# BMS_Master.net
KiCad netlist of a schematic drawn in EAGLE
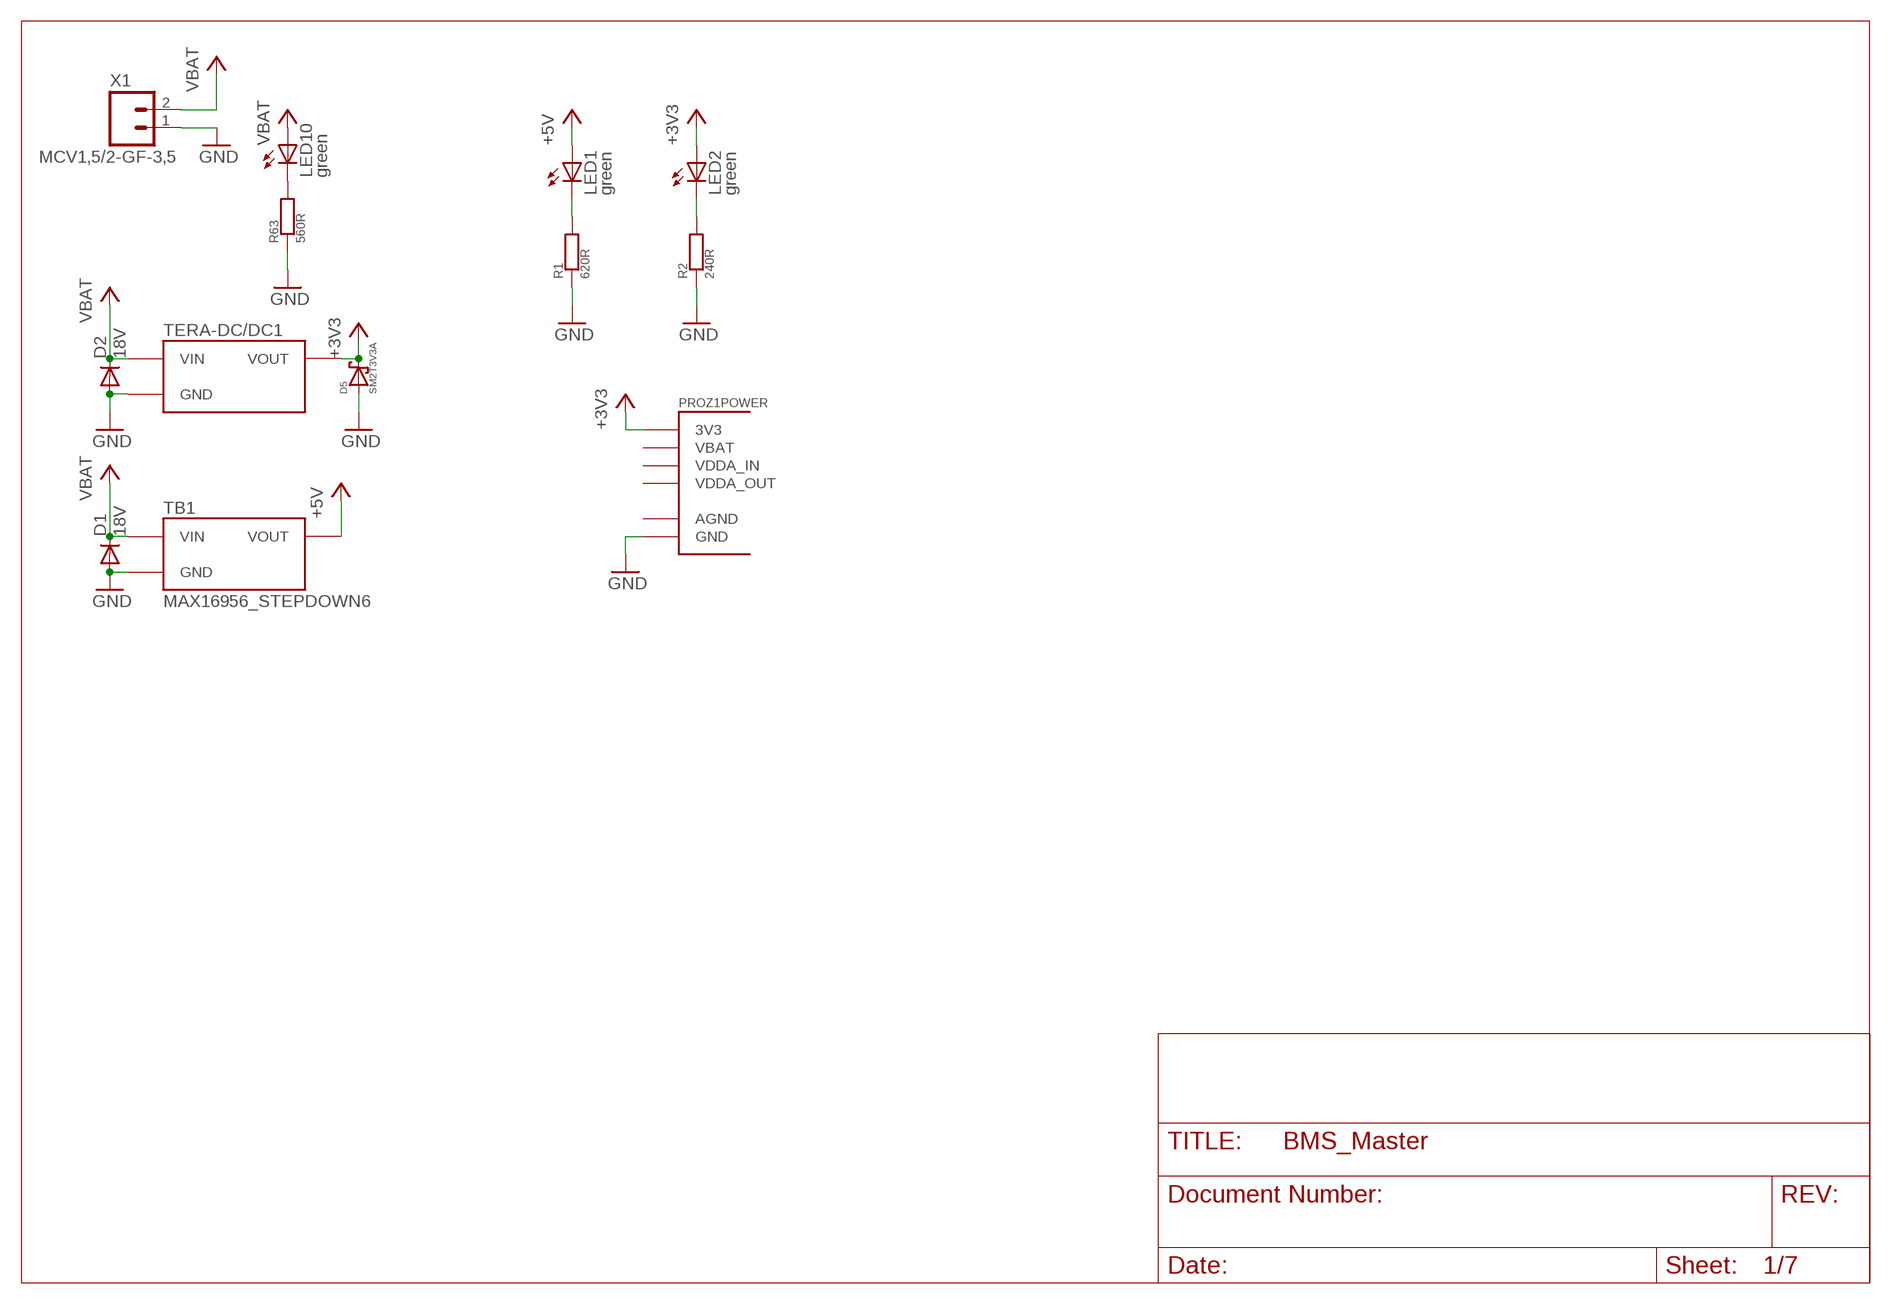
[diagram p0: schematic, sheet 1]
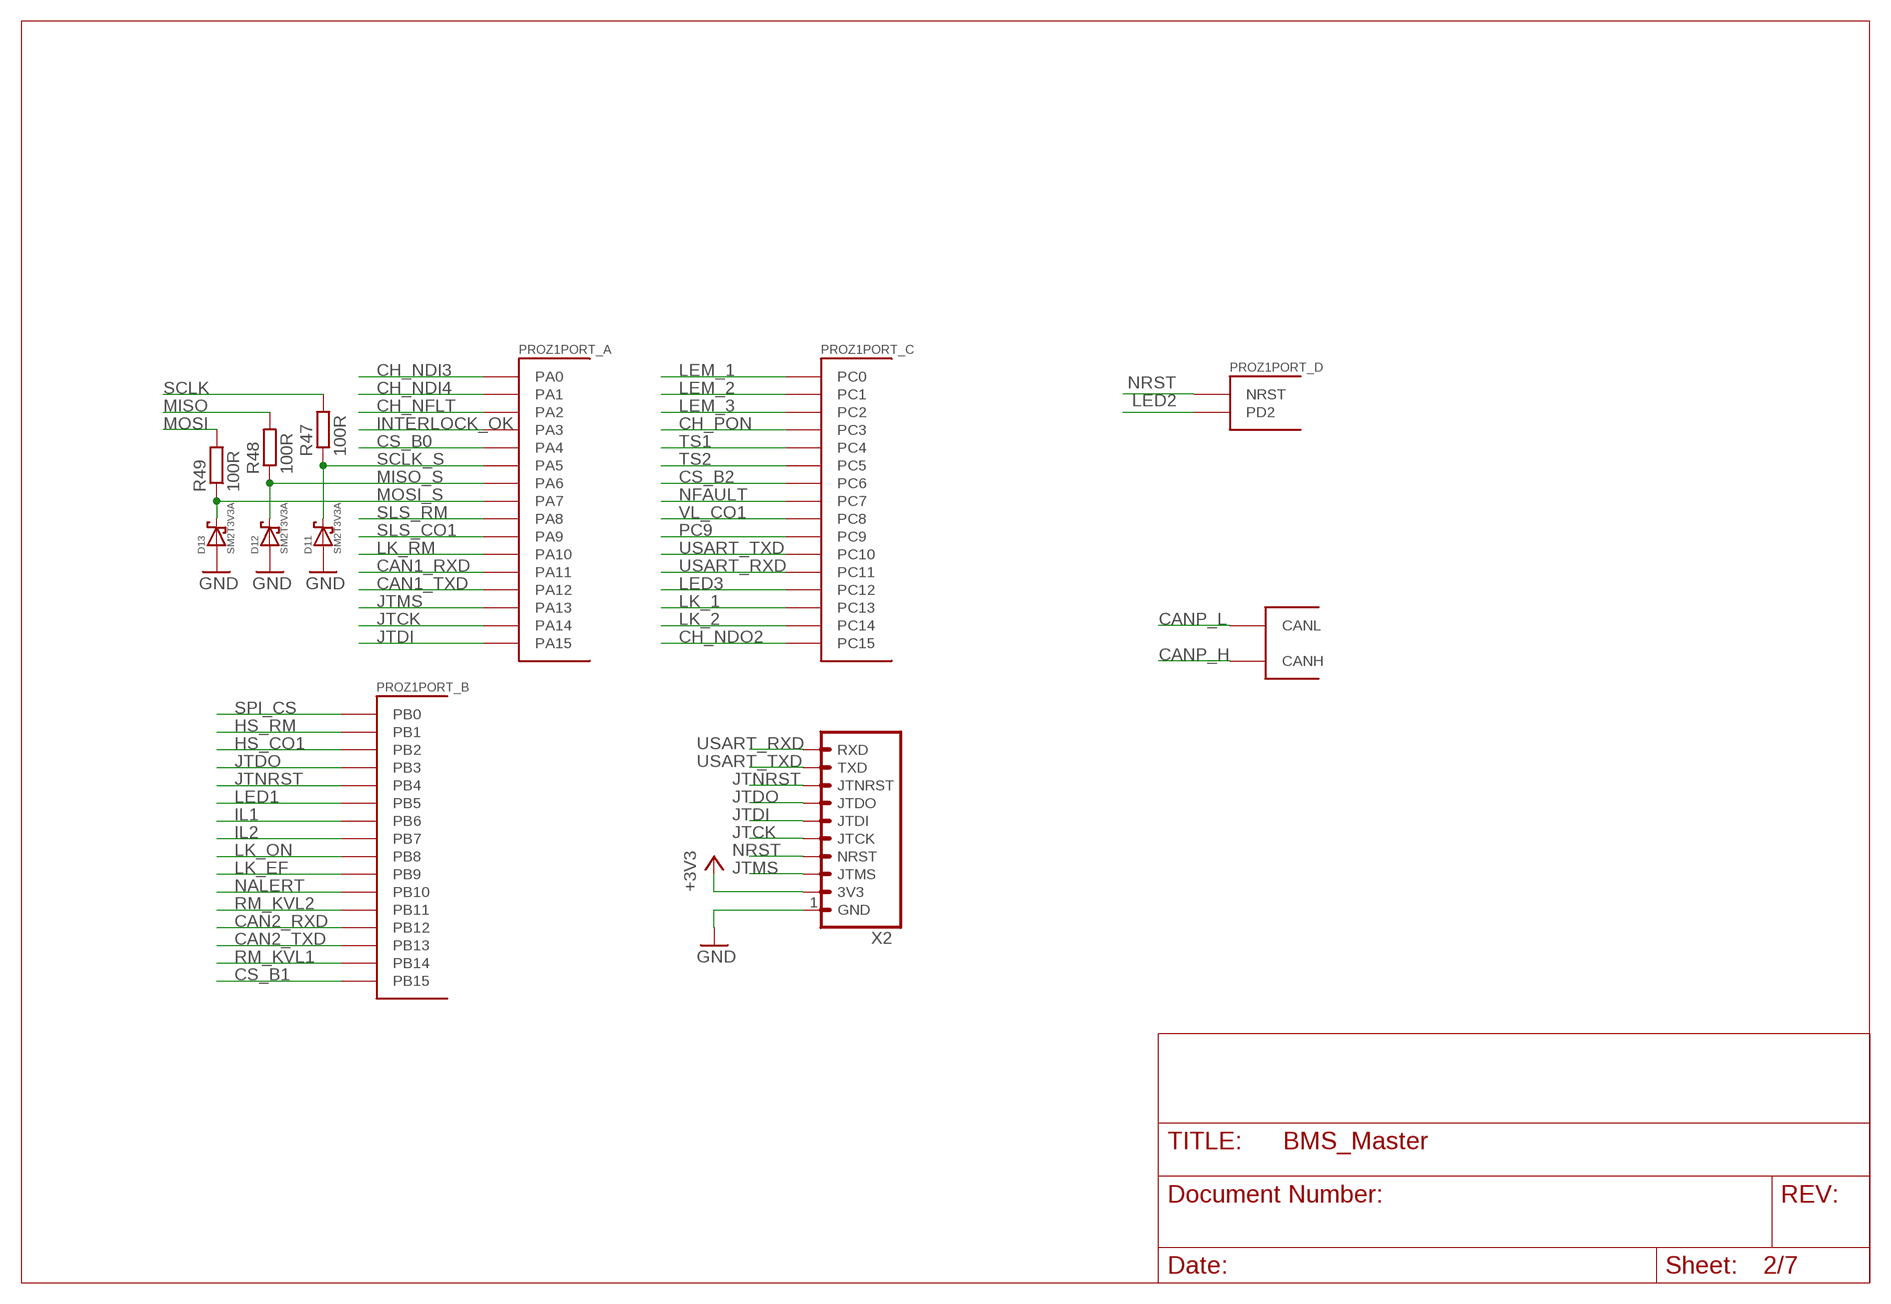
[diagram p1: schematic, sheet 2]
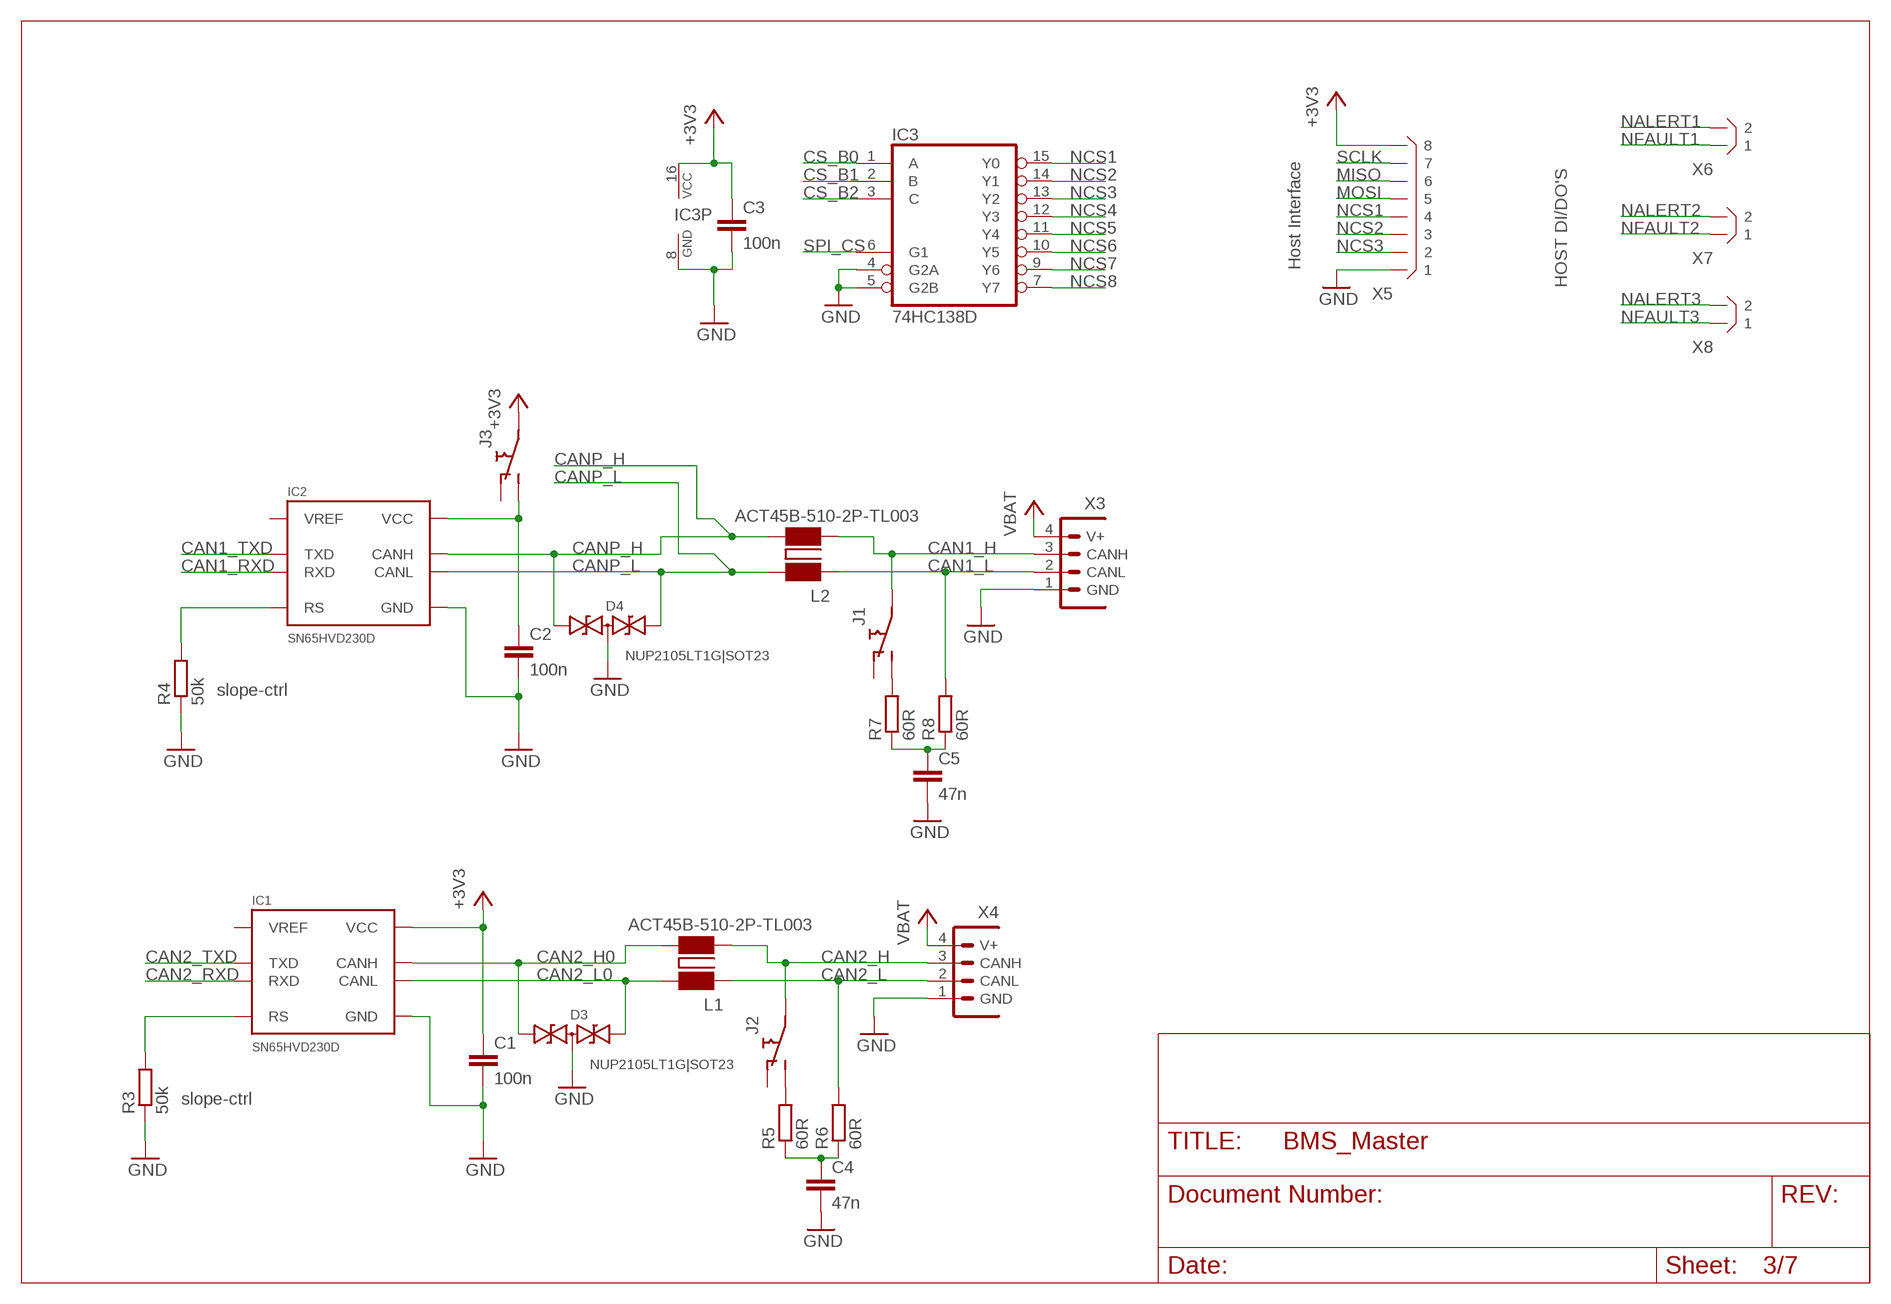
[diagram p2: schematic, sheet 3]
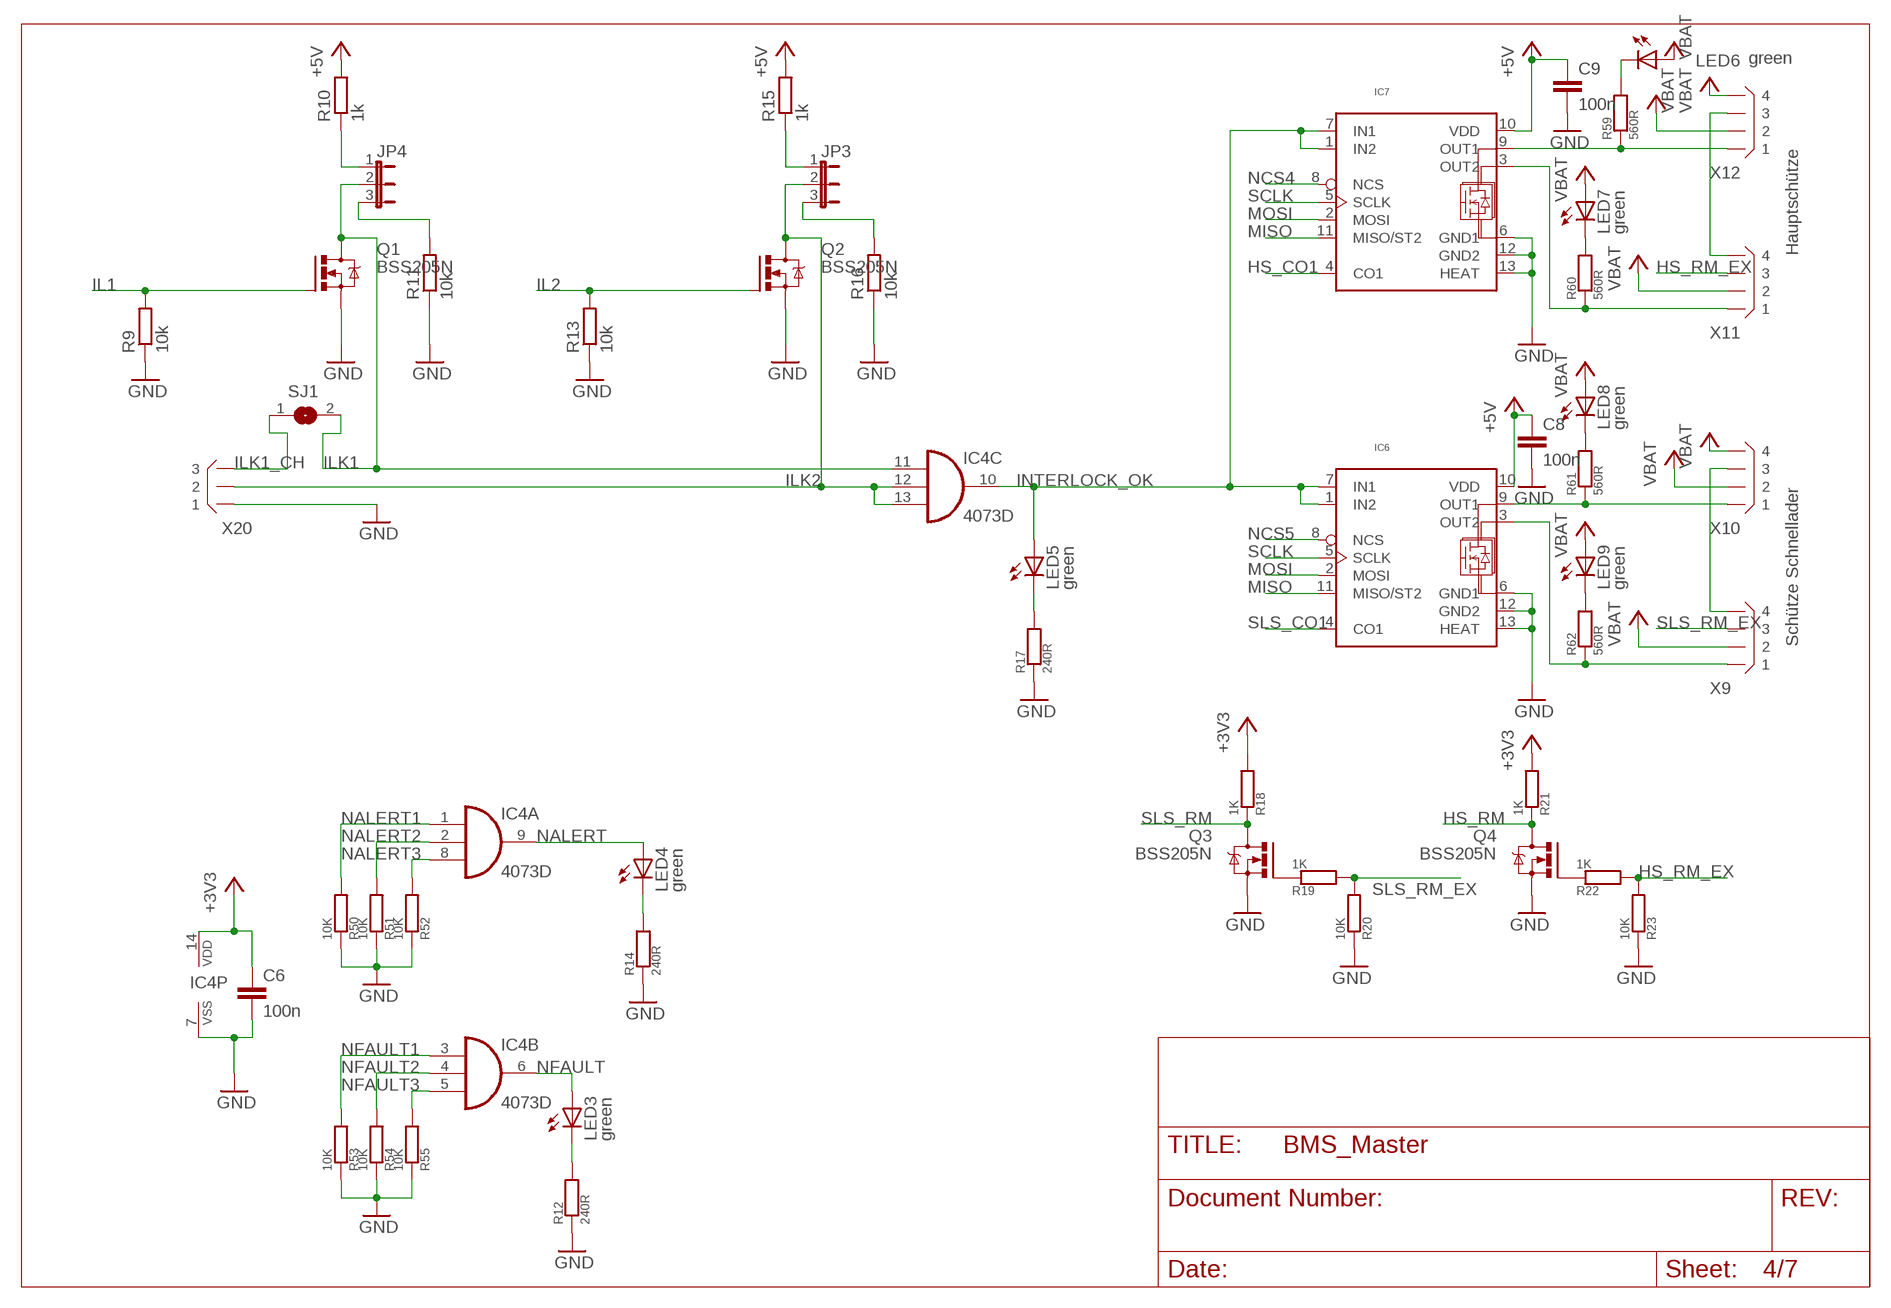
[diagram p3: schematic, sheet 4]
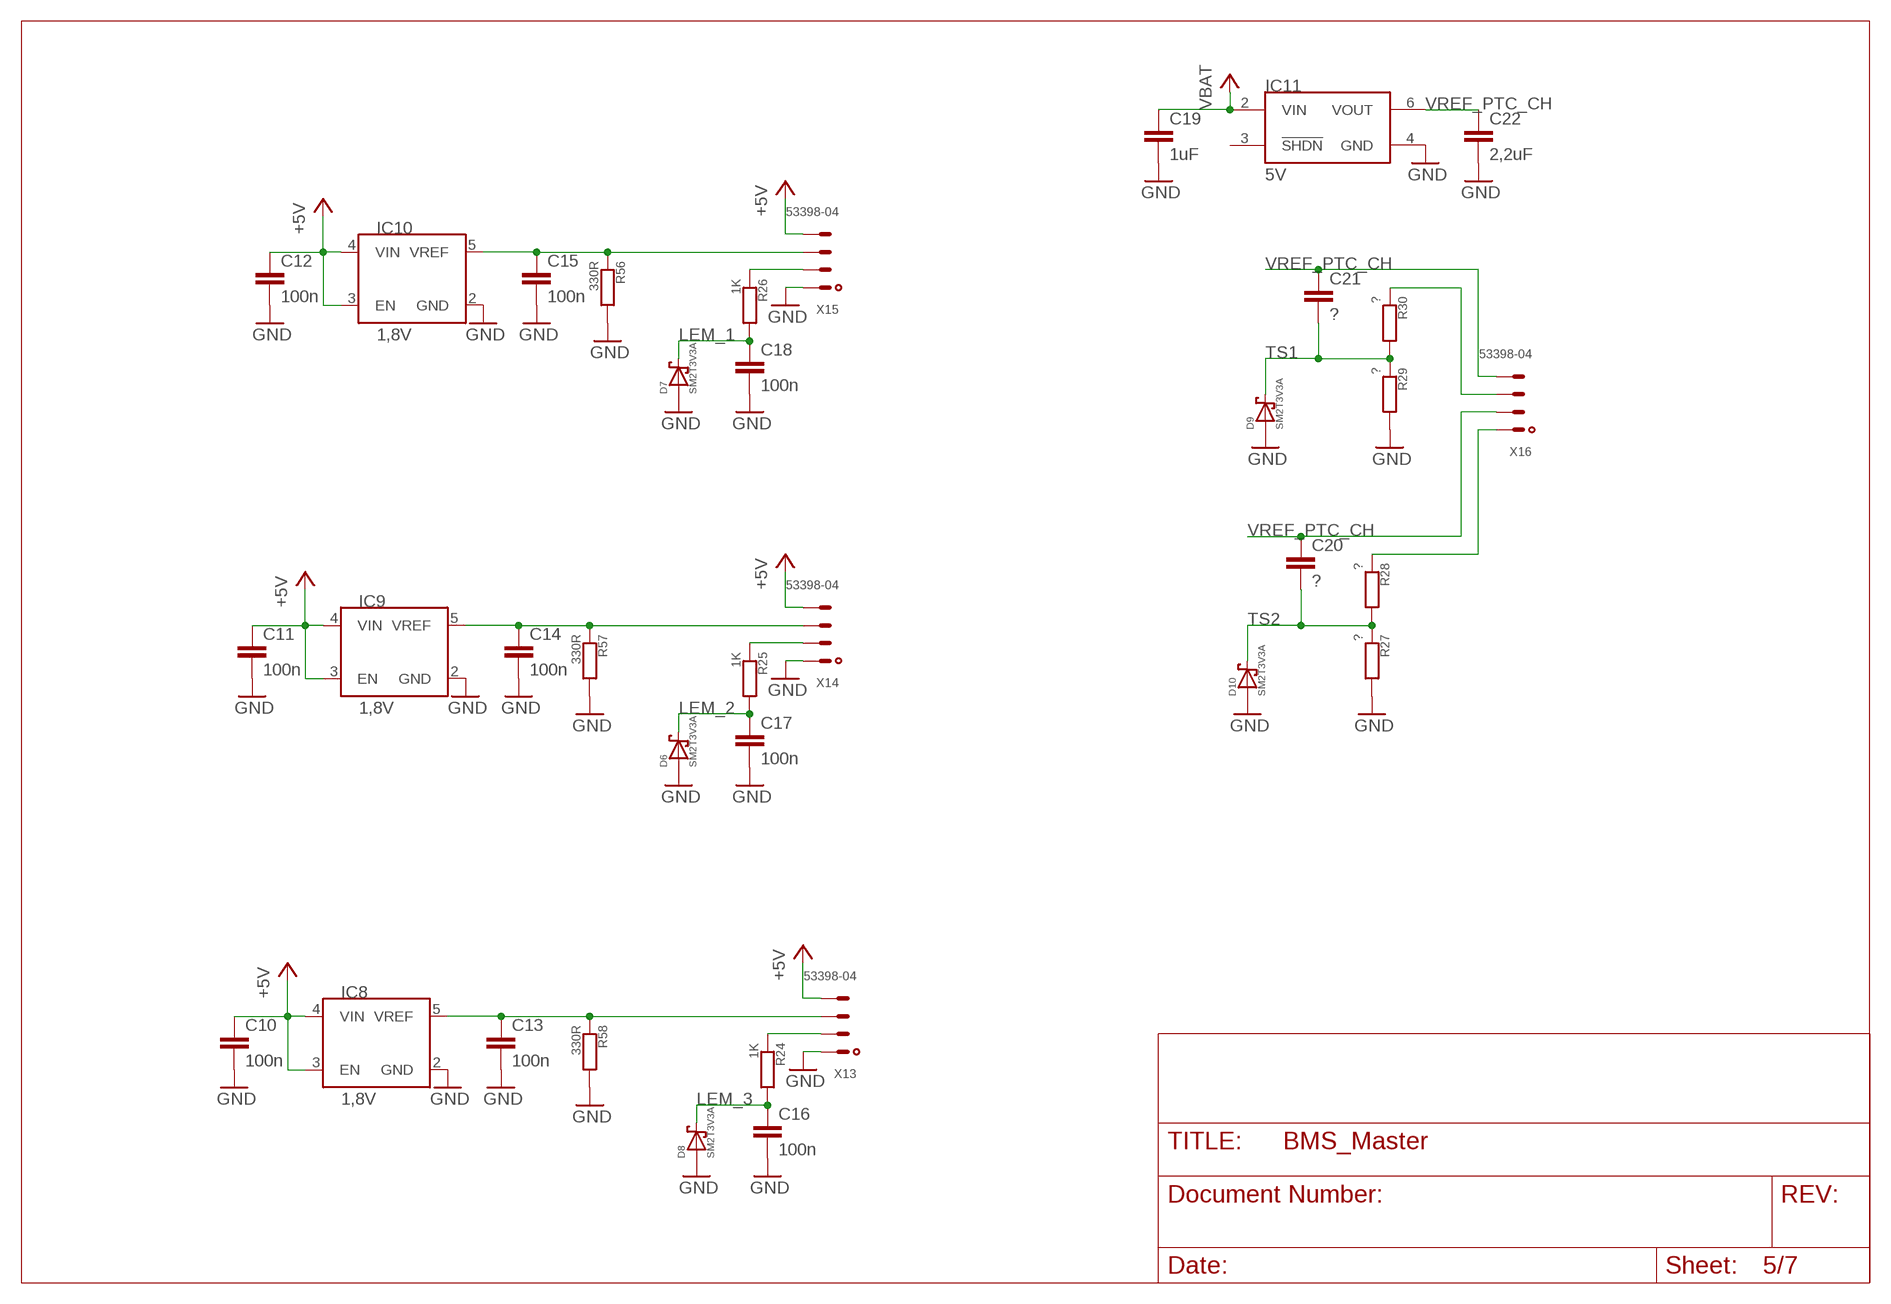
[diagram p4: schematic, sheet 5]
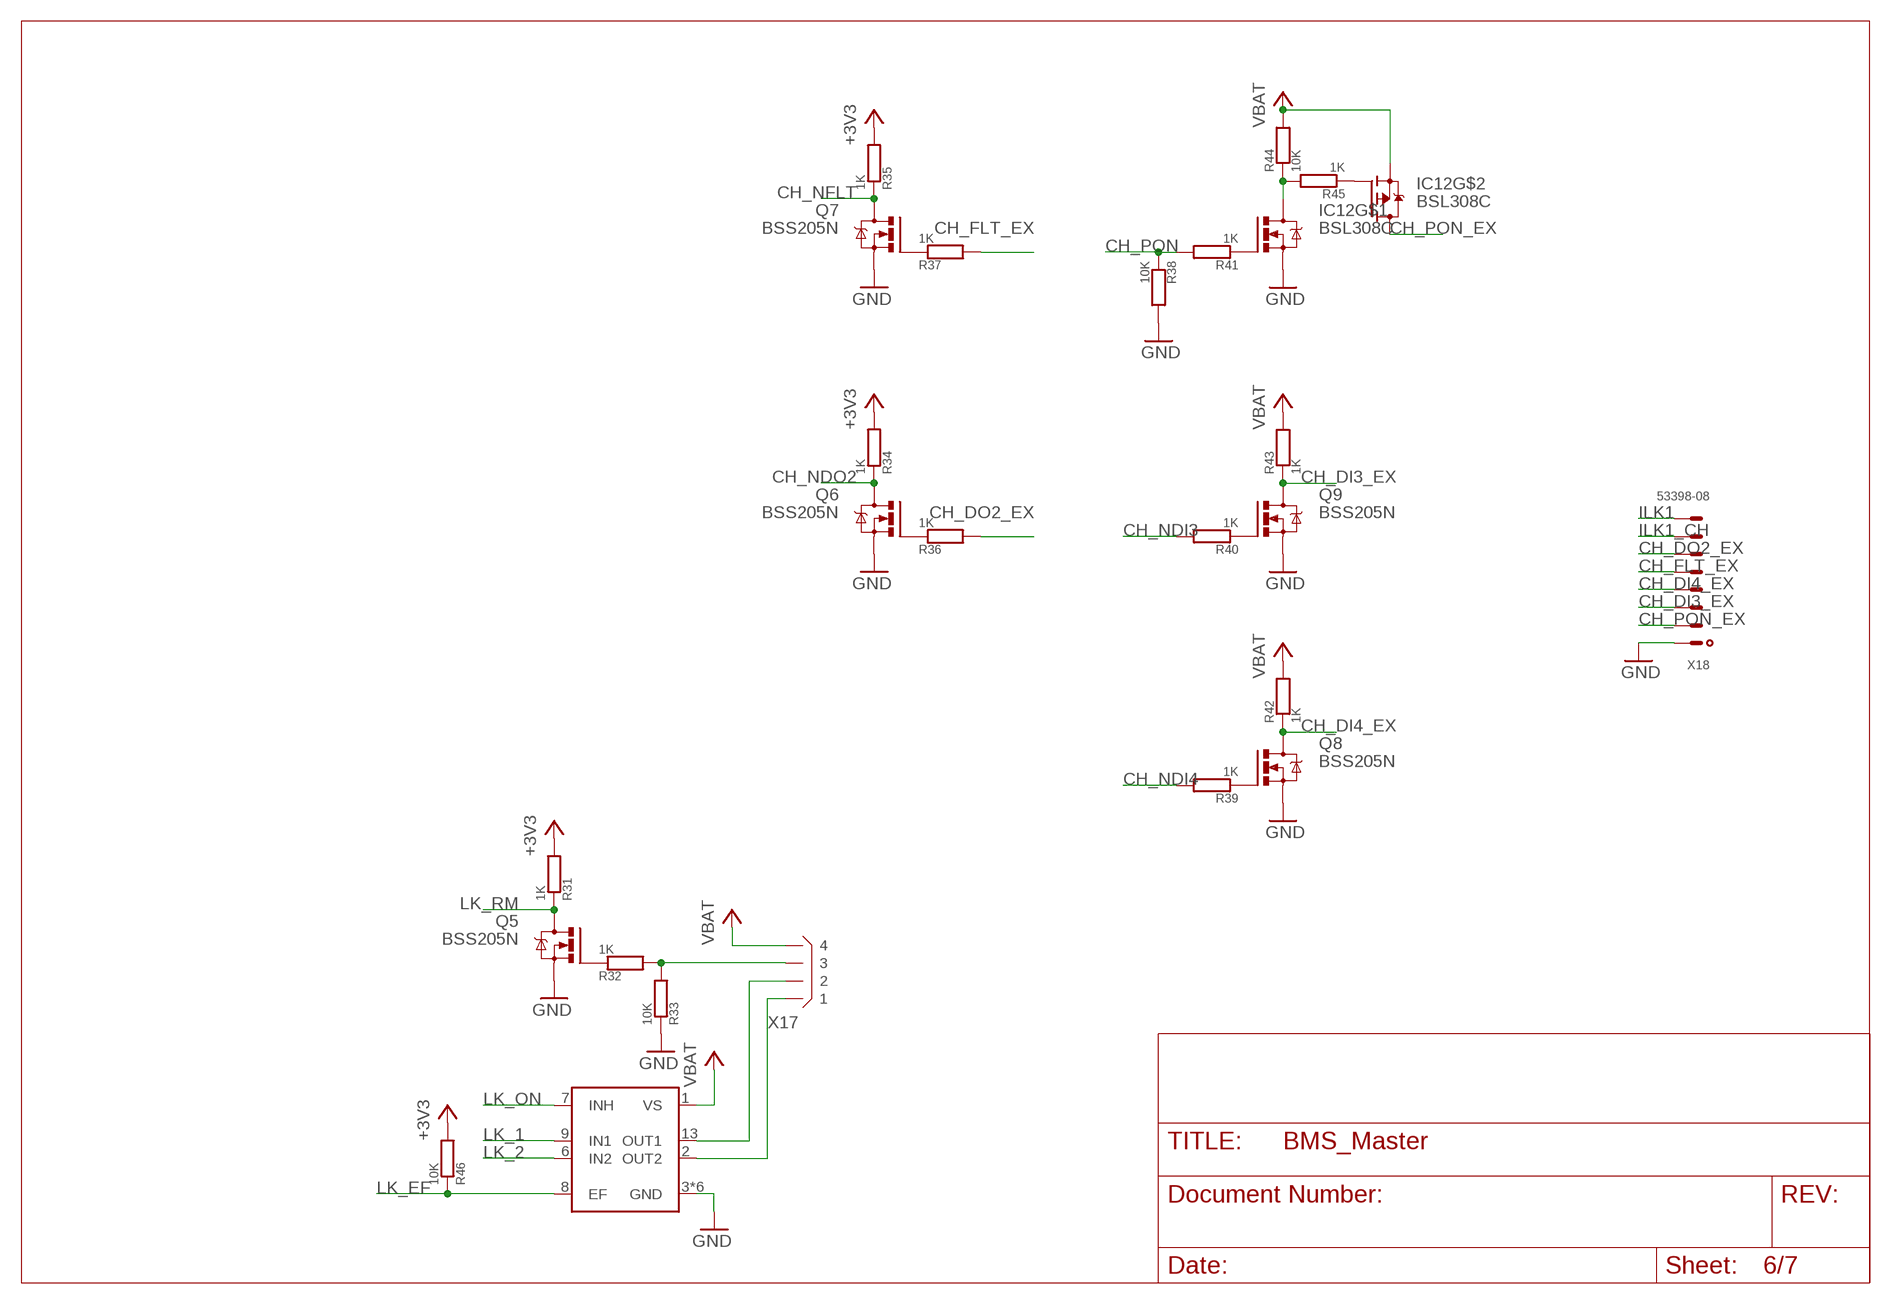
[diagram p5: schematic, sheet 6]
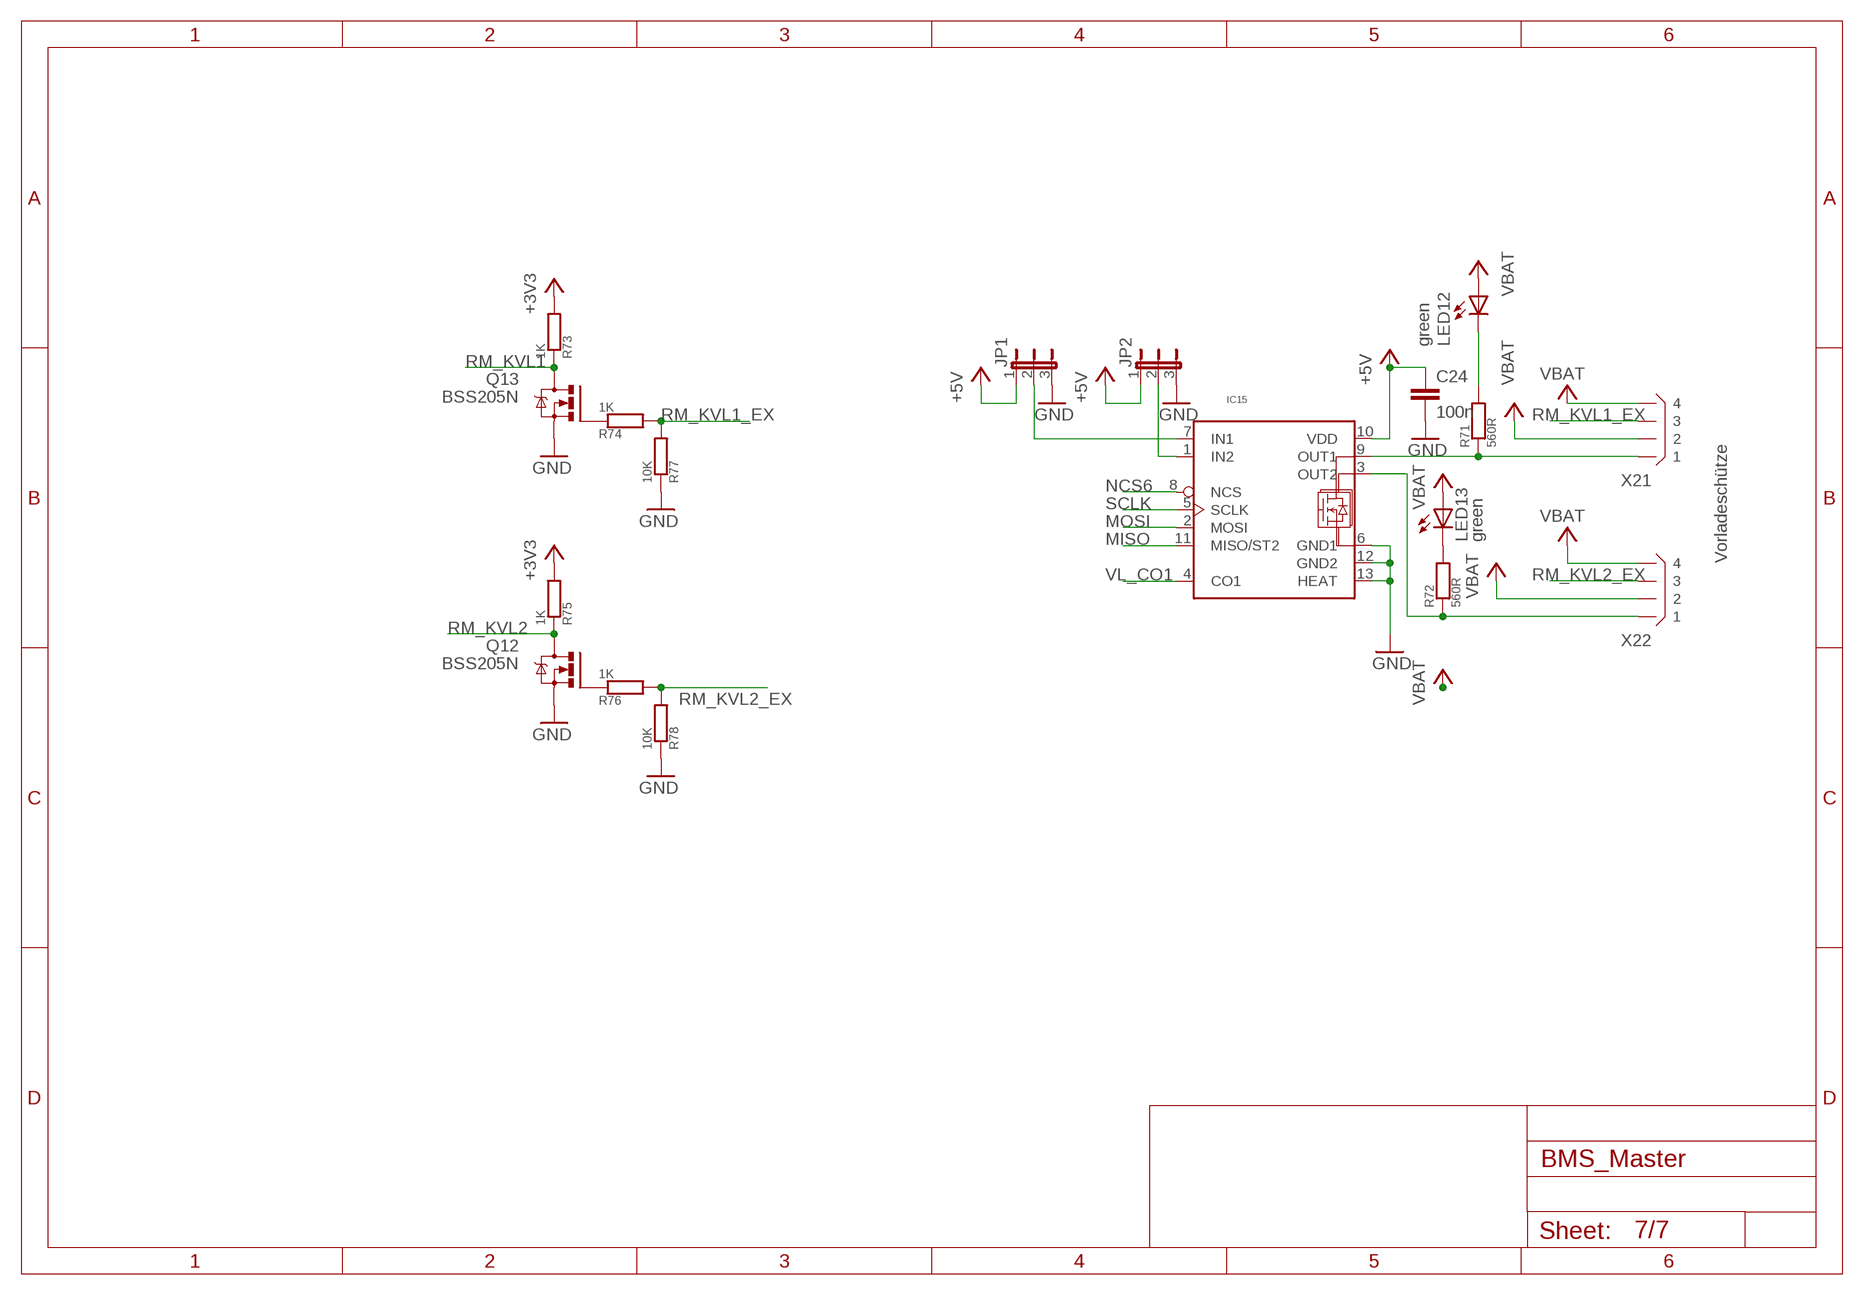
[diagram p6: schematic, sheet 7]

(export (version "E")
  (design (tool "Eeschema 10.0.6"))
  (components
    (comp (ref "D11")
      (value "SM2T3V3A")
      (footprint "eagle-import:SM2T3V3A")
      (libsource (lib "eagle-import") (part "SM2T3V3A"))
    )
    (comp (ref "D12")
      (value "SM2T3V3A")
      (footprint "eagle-import:SM2T3V3A")
      (libsource (lib "eagle-import") (part "SM2T3V3A"))
    )
    (comp (ref "D13")
      (value "SM2T3V3A")
      (footprint "eagle-import:SM2T3V3A")
      (libsource (lib "eagle-import") (part "SM2T3V3A"))
    )
    (comp (ref "PROZ1")
      (value "STM32F4_PROZESSORBOARDRPZ")
      (footprint "eagle-import:STM32F4_PROZESSORBOARD")
      (libsource (lib "eagle-import") (part "STM32F4_PROZESSORBOARDRPZ"))
    )
    (comp (ref "R47")
      (value "100R")
      (footprint "eagle-import:R0805")
      (libsource (lib "eagle-import") (part "R-EU_R0805"))
    )
    (comp (ref "R48")
      (value "100R")
      (footprint "eagle-import:R0805")
      (libsource (lib "eagle-import") (part "R-EU_R0805"))
    )
    (comp (ref "R49")
      (value "100R")
      (footprint "eagle-import:R0805")
      (libsource (lib "eagle-import") (part "R-EU_R0805"))
    )
    (comp (ref "X2")
      (value "TERA-PROG-DEBUG-10GERADE")
      (footprint "eagle-import:90130-1110")
      (libsource (lib "eagle-import") (part "TERA-PROG-DEBUG-10GERADE"))
    )
    (comp (ref "C24")
      (value "100n")
      (footprint "eagle-import:C0603")
      (libsource (lib "eagle-import") (part "C-EUC0603"))
    )
    (comp (ref "IC15")
      (value "TLE8102SGN")
      (footprint "eagle-import:INF-PG-DSO-12-11_N_1PRIMARY")
      (libsource (lib "eagle-import") (part "TLE8102SGN"))
    )
    (comp (ref "JP1")
      (value "JUMPER_OR")
      (footprint "eagle-import:JP2_OCT")
      (libsource (lib "eagle-import") (part "JUMPER_OR"))
    )
    (comp (ref "JP2")
      (value "JUMPER_OR")
      (footprint "eagle-import:JP2_OCT")
      (libsource (lib "eagle-import") (part "JUMPER_OR"))
    )
    (comp (ref "LED12")
      (value "green")
      (footprint "eagle-import:CHIP-LED0805")
      (libsource (lib "eagle-import") (part "LEDCHIP-LED0805"))
    )
    (comp (ref "LED13")
      (value "green")
      (footprint "eagle-import:CHIP-LED0805")
      (libsource (lib "eagle-import") (part "LEDCHIP-LED0805"))
    )
    (comp (ref "Q12")
      (value "BSS205N")
      (footprint "eagle-import:SOT23")
      (libsource (lib "eagle-import") (part "BSS205N"))
    )
    (comp (ref "Q13")
      (value "BSS205N")
      (footprint "eagle-import:SOT23")
      (libsource (lib "eagle-import") (part "BSS205N"))
    )
    (comp (ref "R71")
      (value "560R")
      (footprint "eagle-import:R0805")
      (libsource (lib "eagle-import") (part "R"))
    )
    (comp (ref "R72")
      (value "560R")
      (footprint "eagle-import:R0805")
      (libsource (lib "eagle-import") (part "R"))
    )
    (comp (ref "R73")
      (value "1K")
      (footprint "eagle-import:R0805")
      (libsource (lib "eagle-import") (part "R"))
    )
    (comp (ref "R74")
      (value "1K")
      (footprint "eagle-import:R0805")
      (libsource (lib "eagle-import") (part "R"))
    )
    (comp (ref "R75")
      (value "1K")
      (footprint "eagle-import:R0805")
      (libsource (lib "eagle-import") (part "R"))
    )
    (comp (ref "R76")
      (value "1K")
      (footprint "eagle-import:R0805")
      (libsource (lib "eagle-import") (part "R"))
    )
    (comp (ref "R77")
      (value "10K")
      (footprint "eagle-import:R0805")
      (libsource (lib "eagle-import") (part "R"))
    )
    (comp (ref "R78")
      (value "10K")
      (footprint "eagle-import:R0805")
      (libsource (lib "eagle-import") (part "R"))
    )
    (comp (ref "X21")
      (value "B4B-XH")
      (footprint "eagle-import:B4B-XH")
      (libsource (lib "eagle-import") (part "?4B-XHB"))
    )
    (comp (ref "X22")
      (value "B4B-XH")
      (footprint "eagle-import:B4B-XH")
      (libsource (lib "eagle-import") (part "?4B-XHB"))
    )
    (comp (ref "C10")
      (value "100n")
      (footprint "eagle-import:C0805")
      (libsource (lib "eagle-import") (part "C-EUC0805"))
    )
    (comp (ref "C11")
      (value "100n")
      (footprint "eagle-import:C0805")
      (libsource (lib "eagle-import") (part "C-EUC0805"))
    )
    (comp (ref "C12")
      (value "100n")
      (footprint "eagle-import:C0805")
      (libsource (lib "eagle-import") (part "C-EUC0805"))
    )
    (comp (ref "C13")
      (value "100n")
      (footprint "eagle-import:C0805")
      (libsource (lib "eagle-import") (part "C-EUC0805"))
    )
    (comp (ref "C14")
      (value "100n")
      (footprint "eagle-import:C0805")
      (libsource (lib "eagle-import") (part "C-EUC0805"))
    )
    (comp (ref "C15")
      (value "100n")
      (footprint "eagle-import:C0805")
      (libsource (lib "eagle-import") (part "C-EUC0805"))
    )
    (comp (ref "C16")
      (value "100n")
      (footprint "eagle-import:C0805")
      (libsource (lib "eagle-import") (part "C-EUC0805"))
    )
    (comp (ref "C17")
      (value "100n")
      (footprint "eagle-import:C0805")
      (libsource (lib "eagle-import") (part "C-EUC0805"))
    )
    (comp (ref "C18")
      (value "100n")
      (footprint "eagle-import:C0805")
      (libsource (lib "eagle-import") (part "C-EUC0805"))
    )
    (comp (ref "C19")
      (value "1uF")
      (footprint "eagle-import:C0805")
      (libsource (lib "eagle-import") (part "C-EUC0805"))
    )
    (comp (ref "C20")
      (value "?")
      (footprint "eagle-import:C0805")
      (libsource (lib "eagle-import") (part "C-EUC0805"))
    )
    (comp (ref "C21")
      (value "?")
      (footprint "eagle-import:C0805")
      (libsource (lib "eagle-import") (part "C-EUC0805"))
    )
    (comp (ref "C22")
      (value "2,2uF")
      (footprint "eagle-import:C0805")
      (libsource (lib "eagle-import") (part "C-EUC0805"))
    )
    (comp (ref "D6")
      (value "SM2T3V3A")
      (footprint "eagle-import:SM2T3V3A")
      (libsource (lib "eagle-import") (part "SM2T3V3A"))
    )
    (comp (ref "D7")
      (value "SM2T3V3A")
      (footprint "eagle-import:SM2T3V3A")
      (libsource (lib "eagle-import") (part "SM2T3V3A"))
    )
    (comp (ref "D8")
      (value "SM2T3V3A")
      (footprint "eagle-import:SM2T3V3A")
      (libsource (lib "eagle-import") (part "SM2T3V3A"))
    )
    (comp (ref "D9")
      (value "SM2T3V3A")
      (footprint "eagle-import:SM2T3V3A")
      (libsource (lib "eagle-import") (part "SM2T3V3A"))
    )
    (comp (ref "D10")
      (value "SM2T3V3A")
      (footprint "eagle-import:SM2T3V3A")
      (libsource (lib "eagle-import") (part "SM2T3V3A"))
    )
    (comp (ref "IC8")
      (value "1,8V")
      (footprint "eagle-import:SOT23-5L")
      (libsource (lib "eagle-import") (part "LM4132L"))
    )
    (comp (ref "IC9")
      (value "1,8V")
      (footprint "eagle-import:SOT23-5L")
      (libsource (lib "eagle-import") (part "LM4132L"))
    )
    (comp (ref "IC10")
      (value "1,8V")
      (footprint "eagle-import:SOT23-5L")
      (libsource (lib "eagle-import") (part "LM4132L"))
    )
    (comp (ref "IC11")
      (value "5V")
      (footprint "eagle-import:SO08")
      (libsource (lib "eagle-import") (part "LT1461"))
    )
    (comp (ref "R24")
      (value "1K")
      (footprint "eagle-import:R0805")
      (libsource (lib "eagle-import") (part "R"))
    )
    (comp (ref "R25")
      (value "1K")
      (footprint "eagle-import:R0805")
      (libsource (lib "eagle-import") (part "R"))
    )
    (comp (ref "R26")
      (value "1K")
      (footprint "eagle-import:R0805")
      (libsource (lib "eagle-import") (part "R"))
    )
    (comp (ref "R27")
      (value "?")
      (footprint "eagle-import:R0805")
      (libsource (lib "eagle-import") (part "R"))
    )
    (comp (ref "R28")
      (value "?")
      (footprint "eagle-import:R0805")
      (libsource (lib "eagle-import") (part "R"))
    )
    (comp (ref "R29")
      (value "?")
      (footprint "eagle-import:R0805")
      (libsource (lib "eagle-import") (part "R"))
    )
    (comp (ref "R30")
      (value "?")
      (footprint "eagle-import:R0805")
      (libsource (lib "eagle-import") (part "R"))
    )
    (comp (ref "R56")
      (value "330R")
      (footprint "eagle-import:R0805")
      (libsource (lib "eagle-import") (part "R"))
    )
    (comp (ref "R57")
      (value "330R")
      (footprint "eagle-import:R0805")
      (libsource (lib "eagle-import") (part "R"))
    )
    (comp (ref "R58")
      (value "330R")
      (footprint "eagle-import:R0805")
      (libsource (lib "eagle-import") (part "R"))
    )
    (comp (ref "X13")
      (value "53398-04")
      (footprint "eagle-import:53398-04")
      (libsource (lib "eagle-import") (part "53?-04398"))
    )
    (comp (ref "X14")
      (value "53398-04")
      (footprint "eagle-import:53398-04")
      (libsource (lib "eagle-import") (part "53?-04398"))
    )
    (comp (ref "X15")
      (value "53398-04")
      (footprint "eagle-import:53398-04")
      (libsource (lib "eagle-import") (part "53?-04398"))
    )
    (comp (ref "X16")
      (value "53398-04")
      (footprint "eagle-import:53398-04")
      (libsource (lib "eagle-import") (part "53?-04398"))
    )
    (comp (ref "C1")
      (value "100n")
      (footprint "eagle-import:C0805")
      (libsource (lib "eagle-import") (part "C-EUC0805"))
    )
    (comp (ref "C2")
      (value "100n")
      (footprint "eagle-import:C0805")
      (libsource (lib "eagle-import") (part "C-EUC0805"))
    )
    (comp (ref "C3")
      (value "100n")
      (footprint "eagle-import:C0805")
      (libsource (lib "eagle-import") (part "C-EUC0805"))
    )
    (comp (ref "C4")
      (value "47n")
      (footprint "eagle-import:C0805")
      (libsource (lib "eagle-import") (part "C-EUC0805"))
    )
    (comp (ref "C5")
      (value "47n")
      (footprint "eagle-import:C0805")
      (libsource (lib "eagle-import") (part "C-EUC0805"))
    )
    (comp (ref "D3")
      (value "NUP2105LT1G|SOT23")
      (footprint "eagle-import:SOT23")
      (libsource (lib "eagle-import") (part "NUP2105LT1G|SOT23"))
    )
    (comp (ref "D4")
      (value "NUP2105LT1G|SOT23")
      (footprint "eagle-import:SOT23")
      (libsource (lib "eagle-import") (part "NUP2105LT1G|SOT23"))
    )
    (comp (ref "IC1")
      (value "SN65HVD230D")
      (footprint "eagle-import:SO08")
      (libsource (lib "eagle-import") (part "SN65HVD23D0"))
    )
    (comp (ref "IC2")
      (value "SN65HVD230D")
      (footprint "eagle-import:SO08")
      (libsource (lib "eagle-import") (part "SN65HVD23D0"))
    )
    (comp (ref "IC3")
      (value "74HC138D")
      (footprint "eagle-import:SO16")
      (libsource (lib "eagle-import") (part "74138DHC"))
    )
    (comp (ref "J1")
      (value "JUMPER_SWITCHS")
      (footprint "eagle-import:J_OR_S")
      (libsource (lib "eagle-import") (part "JUMPER_SWITCHS"))
    )
    (comp (ref "J2")
      (value "JUMPER_SWITCHS")
      (footprint "eagle-import:J_OR_S")
      (libsource (lib "eagle-import") (part "JUMPER_SWITCHS"))
    )
    (comp (ref "J3")
      (value "JUMPER_SWITCHS")
      (footprint "eagle-import:J_OR_S")
      (libsource (lib "eagle-import") (part "JUMPER_SWITCHS"))
    )
    (comp (ref "L1")
      (value "ACT45B-510-2P-TL003")
      (footprint "eagle-import:ACT45B")
      (libsource (lib "eagle-import") (part "ACT45B-510-2P-TL003"))
    )
    (comp (ref "L2")
      (value "ACT45B-510-2P-TL003")
      (footprint "eagle-import:ACT45B")
      (libsource (lib "eagle-import") (part "ACT45B-510-2P-TL003"))
    )
    (comp (ref "R3")
      (value "50k")
      (footprint "eagle-import:R0805")
      (libsource (lib "eagle-import") (part "R-EU_R0805"))
    )
    (comp (ref "R4")
      (value "50k")
      (footprint "eagle-import:R0805")
      (libsource (lib "eagle-import") (part "R-EU_R0805"))
    )
    (comp (ref "R5")
      (value "60R")
      (footprint "eagle-import:R0805")
      (libsource (lib "eagle-import") (part "R-EU_R0805"))
    )
    (comp (ref "R6")
      (value "60R")
      (footprint "eagle-import:R0805")
      (libsource (lib "eagle-import") (part "R-EU_R0805"))
    )
    (comp (ref "R7")
      (value "60R")
      (footprint "eagle-import:R0805")
      (libsource (lib "eagle-import") (part "R-EU_R0805"))
    )
    (comp (ref "R8")
      (value "60R")
      (footprint "eagle-import:R0805")
      (libsource (lib "eagle-import") (part "R-EU_R0805"))
    )
    (comp (ref "X3")
      (value "CIOC_4-1-FV-A_CAN-BELEGUNG")
      (footprint "eagle-import:CIOC_4-1-FV")
      (libsource (lib "eagle-import") (part "CIOC_4-1-FV-A_CAN-BELEGUNG"))
    )
    (comp (ref "X4")
      (value "CIOC_4-1-FV-A_CAN-BELEGUNG")
      (footprint "eagle-import:CIOC_4-1-FV")
      (libsource (lib "eagle-import") (part "CIOC_4-1-FV-A_CAN-BELEGUNG"))
    )
    (comp (ref "X5")
      (value "B8B-XH")
      (footprint "eagle-import:B8B-XH")
      (libsource (lib "eagle-import") (part "?8B-XHB"))
    )
    (comp (ref "X6")
      (value "B2B-XH")
      (footprint "eagle-import:B2B-XH")
      (libsource (lib "eagle-import") (part "?2B-XHB"))
    )
    (comp (ref "X7")
      (value "B2B-XH")
      (footprint "eagle-import:B2B-XH")
      (libsource (lib "eagle-import") (part "?2B-XHB"))
    )
    (comp (ref "X8")
      (value "B2B-XH")
      (footprint "eagle-import:B2B-XH")
      (libsource (lib "eagle-import") (part "?2B-XHB"))
    )
    (comp (ref "IC12")
      (value "BSL308C")
      (footprint "eagle-import:TSOP-6")
      (libsource (lib "eagle-import") (part "BSL308C"))
    )
    (comp (ref "IC13")
      (value "TLE4207GM")
      (footprint "eagle-import:INF-PG-DSO-14-22_M_1PRIMARY")
      (libsource (lib "eagle-import") (part "TLE4207GM"))
    )
    (comp (ref "Q5")
      (value "BSS205N")
      (footprint "eagle-import:SOT23")
      (libsource (lib "eagle-import") (part "BSS205N"))
    )
    (comp (ref "Q6")
      (value "BSS205N")
      (footprint "eagle-import:SOT23")
      (libsource (lib "eagle-import") (part "BSS205N"))
    )
    (comp (ref "Q7")
      (value "BSS205N")
      (footprint "eagle-import:SOT23")
      (libsource (lib "eagle-import") (part "BSS205N"))
    )
    (comp (ref "Q8")
      (value "BSS205N")
      (footprint "eagle-import:SOT23")
      (libsource (lib "eagle-import") (part "BSS205N"))
    )
    (comp (ref "Q9")
      (value "BSS205N")
      (footprint "eagle-import:SOT23")
      (libsource (lib "eagle-import") (part "BSS205N"))
    )
    (comp (ref "R31")
      (value "1K")
      (footprint "eagle-import:R0805")
      (libsource (lib "eagle-import") (part "R"))
    )
    (comp (ref "R32")
      (value "1K")
      (footprint "eagle-import:R0805")
      (libsource (lib "eagle-import") (part "R"))
    )
    (comp (ref "R33")
      (value "10K")
      (footprint "eagle-import:R0805")
      (libsource (lib "eagle-import") (part "R"))
    )
    (comp (ref "R34")
      (value "1K")
      (footprint "eagle-import:R0805")
      (libsource (lib "eagle-import") (part "R"))
    )
    (comp (ref "R35")
      (value "1K")
      (footprint "eagle-import:R0805")
      (libsource (lib "eagle-import") (part "R"))
    )
    (comp (ref "R36")
      (value "1K")
      (footprint "eagle-import:R0805")
      (libsource (lib "eagle-import") (part "R"))
    )
    (comp (ref "R37")
      (value "1K")
      (footprint "eagle-import:R0805")
      (libsource (lib "eagle-import") (part "R"))
    )
    (comp (ref "R38")
      (value "10K")
      (footprint "eagle-import:R0805")
      (libsource (lib "eagle-import") (part "R"))
    )
    (comp (ref "R39")
      (value "1K")
      (footprint "eagle-import:R0805")
      (libsource (lib "eagle-import") (part "R"))
    )
    (comp (ref "R40")
      (value "1K")
      (footprint "eagle-import:R0805")
      (libsource (lib "eagle-import") (part "R"))
    )
    (comp (ref "R41")
      (value "1K")
      (footprint "eagle-import:R0805")
      (libsource (lib "eagle-import") (part "R"))
    )
    (comp (ref "R42")
      (value "1K")
      (footprint "eagle-import:R0805")
      (libsource (lib "eagle-import") (part "R"))
    )
    (comp (ref "R43")
      (value "1K")
      (footprint "eagle-import:R0805")
      (libsource (lib "eagle-import") (part "R"))
    )
    (comp (ref "R44")
      (value "10K")
      (footprint "eagle-import:R0805")
      (libsource (lib "eagle-import") (part "R"))
    )
    (comp (ref "R45")
      (value "1K")
      (footprint "eagle-import:R0805")
      (libsource (lib "eagle-import") (part "R"))
    )
    (comp (ref "R46")
      (value "10K")
      (footprint "eagle-import:R0805")
      (libsource (lib "eagle-import") (part "R"))
    )
    (comp (ref "X17")
      (value "B4B-XH")
      (footprint "eagle-import:B4B-XH")
      (libsource (lib "eagle-import") (part "?4B-XHB"))
    )
    (comp (ref "X18")
      (value "53398-08")
      (footprint "eagle-import:53398-08")
      (libsource (lib "eagle-import") (part "53?-08398"))
    )
    (comp (ref "C6")
      (value "100n")
      (footprint "eagle-import:C0805")
      (libsource (lib "eagle-import") (part "C-EUC0805"))
    )
    (comp (ref "C8")
      (value "100n")
      (footprint "eagle-import:C0603")
      (libsource (lib "eagle-import") (part "C-EUC0603"))
    )
    (comp (ref "C9")
      (value "100n")
      (footprint "eagle-import:C0603")
      (libsource (lib "eagle-import") (part "C-EUC0603"))
    )
    (comp (ref "IC4")
      (value "4073D")
      (footprint "eagle-import:SO14")
      (libsource (lib "eagle-import") (part "4073D"))
    )
    (comp (ref "IC6")
      (value "TLE8102SGN")
      (footprint "eagle-import:INF-PG-DSO-12-11_N_1PRIMARY")
      (libsource (lib "eagle-import") (part "TLE8102SGN"))
    )
    (comp (ref "IC7")
      (value "TLE8102SGN")
      (footprint "eagle-import:INF-PG-DSO-12-11_N_1PRIMARY")
      (libsource (lib "eagle-import") (part "TLE8102SGN"))
    )
    (comp (ref "JP3")
      (value "JUMPER_OR")
      (footprint "eagle-import:JP2_OCT")
      (libsource (lib "eagle-import") (part "JUMPER_OR"))
    )
    (comp (ref "JP4")
      (value "JUMPER_OR")
      (footprint "eagle-import:JP2_OCT")
      (libsource (lib "eagle-import") (part "JUMPER_OR"))
    )
    (comp (ref "LED3")
      (value "green")
      (footprint "eagle-import:CHIPLED_0805")
      (libsource (lib "eagle-import") (part "LEDCHIPLED_0805"))
    )
    (comp (ref "LED4")
      (value "green")
      (footprint "eagle-import:CHIPLED_0805")
      (libsource (lib "eagle-import") (part "LEDCHIPLED_0805"))
    )
    (comp (ref "LED5")
      (value "green")
      (footprint "eagle-import:CHIPLED_0805")
      (libsource (lib "eagle-import") (part "LEDCHIPLED_0805"))
    )
    (comp (ref "LED6")
      (value "green")
      (footprint "eagle-import:CHIP-LED0805")
      (libsource (lib "eagle-import") (part "LEDCHIP-LED0805"))
    )
    (comp (ref "LED7")
      (value "green")
      (footprint "eagle-import:CHIP-LED0805")
      (libsource (lib "eagle-import") (part "LEDCHIP-LED0805"))
    )
    (comp (ref "LED8")
      (value "green")
      (footprint "eagle-import:CHIP-LED0805")
      (libsource (lib "eagle-import") (part "LEDCHIP-LED0805"))
    )
    (comp (ref "LED9")
      (value "green")
      (footprint "eagle-import:CHIP-LED0805")
      (libsource (lib "eagle-import") (part "LEDCHIP-LED0805"))
    )
    (comp (ref "Q1")
      (value "BSS205N")
      (footprint "eagle-import:SOT23")
      (libsource (lib "eagle-import") (part "BSS205N"))
    )
    (comp (ref "Q2")
      (value "BSS205N")
      (footprint "eagle-import:SOT23")
      (libsource (lib "eagle-import") (part "BSS205N"))
    )
    (comp (ref "Q3")
      (value "BSS205N")
      (footprint "eagle-import:SOT23")
      (libsource (lib "eagle-import") (part "BSS205N"))
    )
    (comp (ref "Q4")
      (value "BSS205N")
      (footprint "eagle-import:SOT23")
      (libsource (lib "eagle-import") (part "BSS205N"))
    )
    (comp (ref "R9")
      (value "10k")
      (footprint "eagle-import:R0805")
      (libsource (lib "eagle-import") (part "R-EU_R0805"))
    )
    (comp (ref "R10")
      (value "1k")
      (footprint "eagle-import:R0805")
      (libsource (lib "eagle-import") (part "R-EU_R0805"))
    )
    (comp (ref "R11")
      (value "10k")
      (footprint "eagle-import:R0805")
      (libsource (lib "eagle-import") (part "R-EU_R0805"))
    )
    (comp (ref "R12")
      (value "240R")
      (footprint "eagle-import:R0805")
      (libsource (lib "eagle-import") (part "R"))
    )
    (comp (ref "R13")
      (value "10k")
      (footprint "eagle-import:R0805")
      (libsource (lib "eagle-import") (part "R-EU_R0805"))
    )
    (comp (ref "R14")
      (value "240R")
      (footprint "eagle-import:R0805")
      (libsource (lib "eagle-import") (part "R"))
    )
    (comp (ref "R15")
      (value "1k")
      (footprint "eagle-import:R0805")
      (libsource (lib "eagle-import") (part "R-EU_R0805"))
    )
    (comp (ref "R16")
      (value "10k")
      (footprint "eagle-import:R0805")
      (libsource (lib "eagle-import") (part "R-EU_R0805"))
    )
    (comp (ref "R17")
      (value "240R")
      (footprint "eagle-import:R0805")
      (libsource (lib "eagle-import") (part "R"))
    )
    (comp (ref "R18")
      (value "1K")
      (footprint "eagle-import:R0805")
      (libsource (lib "eagle-import") (part "R"))
    )
    (comp (ref "R19")
      (value "1K")
      (footprint "eagle-import:R0805")
      (libsource (lib "eagle-import") (part "R"))
    )
    (comp (ref "R20")
      (value "10K")
      (footprint "eagle-import:R0805")
      (libsource (lib "eagle-import") (part "R"))
    )
    (comp (ref "R21")
      (value "1K")
      (footprint "eagle-import:R0805")
      (libsource (lib "eagle-import") (part "R"))
    )
    (comp (ref "R22")
      (value "1K")
      (footprint "eagle-import:R0805")
      (libsource (lib "eagle-import") (part "R"))
    )
    (comp (ref "R23")
      (value "10K")
      (footprint "eagle-import:R0805")
      (libsource (lib "eagle-import") (part "R"))
    )
    (comp (ref "R50")
      (value "10K")
      (footprint "eagle-import:R0805")
      (libsource (lib "eagle-import") (part "R"))
    )
    (comp (ref "R51")
      (value "10K")
      (footprint "eagle-import:R0805")
      (libsource (lib "eagle-import") (part "R"))
    )
    (comp (ref "R52")
      (value "10K")
      (footprint "eagle-import:R0805")
      (libsource (lib "eagle-import") (part "R"))
    )
    (comp (ref "R53")
      (value "10K")
      (footprint "eagle-import:R0805")
      (libsource (lib "eagle-import") (part "R"))
    )
    (comp (ref "R54")
      (value "10K")
      (footprint "eagle-import:R0805")
      (libsource (lib "eagle-import") (part "R"))
    )
    (comp (ref "R55")
      (value "10K")
      (footprint "eagle-import:R0805")
      (libsource (lib "eagle-import") (part "R"))
    )
    (comp (ref "R59")
      (value "560R")
      (footprint "eagle-import:R0805")
      (libsource (lib "eagle-import") (part "R"))
    )
    (comp (ref "R60")
      (value "560R")
      (footprint "eagle-import:R0805")
      (libsource (lib "eagle-import") (part "R"))
    )
    (comp (ref "R61")
      (value "560R")
      (footprint "eagle-import:R0805")
      (libsource (lib "eagle-import") (part "R"))
    )
    (comp (ref "R62")
      (value "560R")
      (footprint "eagle-import:R0805")
      (libsource (lib "eagle-import") (part "R"))
    )
    (comp (ref "SJ1") (value "SJ") (footprint "eagle-import:SJ") (libsource (lib "eagle-import") (part "SJ")))
    (comp (ref "X9")
      (value "B4B-XH")
      (footprint "eagle-import:B4B-XH")
      (libsource (lib "eagle-import") (part "?4B-XHB"))
    )
    (comp (ref "X10")
      (value "B4B-XH")
      (footprint "eagle-import:B4B-XH")
      (libsource (lib "eagle-import") (part "?4B-XHB"))
    )
    (comp (ref "X11")
      (value "B4B-XH")
      (footprint "eagle-import:B4B-XH")
      (libsource (lib "eagle-import") (part "?4B-XHB"))
    )
    (comp (ref "X12")
      (value "B4B-XH")
      (footprint "eagle-import:B4B-XH")
      (libsource (lib "eagle-import") (part "?4B-XHB"))
    )
    (comp (ref "X20")
      (value "B3B-XH")
      (footprint "eagle-import:B3B-XH")
      (libsource (lib "eagle-import") (part "?3B-XHB"))
    )
    (comp (ref "D1")
      (value "18V")
      (footprint "eagle-import:DO214AA")
      (libsource (lib "eagle-import") (part "DIODE-DO214AA"))
    )
    (comp (ref "D2")
      (value "18V")
      (footprint "eagle-import:DO214AA")
      (libsource (lib "eagle-import") (part "DIODE-DO214AA"))
    )
    (comp (ref "D5")
      (value "SM2T3V3A")
      (footprint "eagle-import:SM2T3V3A")
      (libsource (lib "eagle-import") (part "SM2T3V3A"))
    )
    (comp (ref "LED1")
      (value "green")
      (footprint "eagle-import:CHIP-LED0805")
      (libsource (lib "eagle-import") (part "LEDCHIP-LED0805"))
    )
    (comp (ref "LED2")
      (value "green")
      (footprint "eagle-import:CHIP-LED0805")
      (libsource (lib "eagle-import") (part "LEDCHIP-LED0805"))
    )
    (comp (ref "LED10")
      (value "green")
      (footprint "eagle-import:CHIP-LED0805")
      (libsource (lib "eagle-import") (part "LEDCHIP-LED0805"))
    )
    (comp (ref "R1")
      (value "620R")
      (footprint "eagle-import:R0805")
      (libsource (lib "eagle-import") (part "R"))
    )
    (comp (ref "R2")
      (value "240R")
      (footprint "eagle-import:R0805")
      (libsource (lib "eagle-import") (part "R"))
    )
    (comp (ref "R63")
      (value "560R")
      (footprint "eagle-import:R0805")
      (libsource (lib "eagle-import") (part "R"))
    )
    (comp (ref "TB1")
      (value "MAX16956_STEPDOWN6")
      (footprint "eagle-import:MAX16956_STEPDOWN6")
      (libsource (lib "eagle-import") (part "MAX16956_STEPDOWN6"))
    )
    (comp (ref "TERA-DC/DC1")
      (value "MAX5035_STEPDOWN3")
      (footprint "eagle-import:MAX5035_STEPDOWN3")
      (libsource (lib "eagle-import") (part "MAX5035_STEPDOWN3"))
    )
    (comp (ref "X1")
      (value "MCV1,5/2-GF-3,5")
      (footprint "eagle-import:MCV1,5_2-GF-3,5")
      (libsource (lib "eagle-import") (part "MCV1,5/2-GF-3,5"))
    )
  )
  (nets
    (net (code "1") (name "+3V3") (class "Default")
      (node (ref "C1") (pin "1") (pinfunction "1_1") (pintype "passive"))
      (node (ref "C3") (pin "1") (pinfunction "1_1") (pintype "passive"))
      (node (ref "C6") (pin "1") (pinfunction "1_1") (pintype "passive"))
      (node (ref "D5") (pin "P$2") (pinfunction "P$2_P$2") (pintype "bidirectional"))
      (node (ref "IC1") (pin "3") (pinfunction "VCC_3") (pintype "power_in"))
      (node (ref "IC3") (pin "16") (pinfunction "VCC_16") (pintype "power_in"))
      (node (ref "IC4") (pin "14") (pinfunction "VDD_14") (pintype "power_in"))
      (node (ref "J3") (pin "P$1") (pinfunction "P$1_P$1") (pintype "bidirectional"))
      (node (ref "LED2") (pin "A") (pinfunction "A_A") (pintype "passive"))
      (node (ref "PROZ1") (pin "45") (pinfunction "3V3_45") (pintype "passive"))
      (node (ref "PROZ1") (pin "46") (pinfunction "3V3_46") (pintype "passive"))
      (node (ref "R18") (pin "2") (pinfunction "2_2") (pintype "passive"))
      (node (ref "R21") (pin "2") (pinfunction "2_2") (pintype "passive"))
      (node (ref "R31") (pin "2") (pinfunction "2_2") (pintype "passive"))
      (node (ref "R34") (pin "2") (pinfunction "2_2") (pintype "passive"))
      (node (ref "R35") (pin "2") (pinfunction "2_2") (pintype "passive"))
      (node (ref "R46") (pin "2") (pinfunction "2_2") (pintype "passive"))
      (node (ref "R73") (pin "2") (pinfunction "2_2") (pintype "passive"))
      (node (ref "R75") (pin "2") (pinfunction "2_2") (pintype "passive"))
      (node (ref "TERA-DC/DC1") (pin "VOUT") (pinfunction "VOUT_VOUT") (pintype "passive"))
      (node (ref "X2") (pin "2") (pinfunction "3V3_2") (pintype "passive"))
      (node (ref "X5") (pin "P$8") (pinfunction "8_P$8") (pintype "bidirectional"))
    )
    (net (code "2") (name "+5V") (class "Default")
      (node (ref "C10") (pin "1") (pinfunction "1_1") (pintype "passive"))
      (node (ref "C11") (pin "1") (pinfunction "1_1") (pintype "passive"))
      (node (ref "C12") (pin "1") (pinfunction "1_1") (pintype "passive"))
      (node (ref "C24") (pin "1") (pinfunction "1_1") (pintype "passive"))
      (node (ref "C8") (pin "1") (pinfunction "1_1") (pintype "passive"))
      (node (ref "C9") (pin "1") (pinfunction "1_1") (pintype "passive"))
      (node (ref "IC10") (pin "3") (pinfunction "EN_3") (pintype "bidirectional"))
      (node (ref "IC10") (pin "4") (pinfunction "VIN_4") (pintype "bidirectional"))
      (node (ref "IC15") (pin "10") (pinfunction "VDD_10") (pintype "bidirectional"))
      (node (ref "IC6") (pin "10") (pinfunction "VDD_10") (pintype "bidirectional"))
      (node (ref "IC7") (pin "10") (pinfunction "VDD_10") (pintype "bidirectional"))
      (node (ref "IC8") (pin "3") (pinfunction "EN_3") (pintype "bidirectional"))
      (node (ref "IC8") (pin "4") (pinfunction "VIN_4") (pintype "bidirectional"))
      (node (ref "IC9") (pin "3") (pinfunction "EN_3") (pintype "bidirectional"))
      (node (ref "IC9") (pin "4") (pinfunction "VIN_4") (pintype "bidirectional"))
      (node (ref "JP1") (pin "1") (pinfunction "1_1") (pintype "passive"))
      (node (ref "JP2") (pin "1") (pinfunction "1_1") (pintype "passive"))
      (node (ref "LED1") (pin "A") (pinfunction "A_A") (pintype "passive"))
      (node (ref "R10") (pin "2") (pinfunction "2_2") (pintype "passive"))
      (node (ref "R15") (pin "2") (pinfunction "2_2") (pintype "passive"))
      (node (ref "TB1") (pin "VOUT") (pinfunction "VOUT_VOUT") (pintype "passive"))
      (node (ref "X13") (pin "4") (pinfunction "4_4") (pintype "passive"))
      (node (ref "X14") (pin "4") (pinfunction "4_4") (pintype "passive"))
      (node (ref "X15") (pin "4") (pinfunction "4_4") (pintype "passive"))
    )
    (net (code "3") (name "CAN1_H") (class "Default")
      (node (ref "J1") (pin "P$1") (pinfunction "P$1_P$1") (pintype "bidirectional"))
      (node (ref "L2") (pin "P$1") (pinfunction "1_P$1") (pintype "passive"))
      (node (ref "X3") (pin "3") (pinfunction "CANH_3") (pintype "passive"))
    )
    (net (code "4") (name "CAN1_L") (class "Default")
      (node (ref "L2") (pin "P$3") (pinfunction "3_P$3") (pintype "passive"))
      (node (ref "R8") (pin "2") (pinfunction "2_2") (pintype "passive"))
      (node (ref "X3") (pin "2") (pinfunction "CANL_2") (pintype "passive"))
    )
    (net (code "5") (name "CAN1_RXD") (class "Default")
      (node (ref "IC2") (pin "4") (pinfunction "RXD_4") (pintype "output"))
      (node (ref "PROZ1") (pin "26") (pinfunction "PA11_26") (pintype "bidirectional"))
    )
    (net (code "6") (name "CAN1_TXD") (class "Default")
      (node (ref "IC2") (pin "1") (pinfunction "TXD_1") (pintype "input"))
      (node (ref "PROZ1") (pin "24") (pinfunction "PA12_24") (pintype "bidirectional"))
    )
    (net (code "7") (name "CAN2_H") (class "Default")
      (node (ref "J2") (pin "P$1") (pinfunction "P$1_P$1") (pintype "bidirectional"))
      (node (ref "L1") (pin "P$1") (pinfunction "1_P$1") (pintype "passive"))
      (node (ref "X4") (pin "3") (pinfunction "CANH_3") (pintype "passive"))
    )
    (net (code "8") (name "CAN2_H0") (class "Default")
      (node (ref "D3") (pin "1") (pinfunction "P$1_1") (pintype "passive"))
      (node (ref "IC1") (pin "7") (pinfunction "CANH_7") (pintype "bidirectional"))
      (node (ref "L1") (pin "P$2") (pinfunction "2_P$2") (pintype "passive"))
    )
    (net (code "9") (name "CAN2_L") (class "Default")
      (node (ref "L1") (pin "P$3") (pinfunction "3_P$3") (pintype "passive"))
      (node (ref "R6") (pin "2") (pinfunction "2_2") (pintype "passive"))
      (node (ref "X4") (pin "2") (pinfunction "CANL_2") (pintype "passive"))
    )
    (net (code "10") (name "CAN2_L0") (class "Default")
      (node (ref "D3") (pin "2") (pinfunction "P$2_2") (pintype "passive"))
      (node (ref "IC1") (pin "6") (pinfunction "CANL_6") (pintype "bidirectional"))
      (node (ref "L1") (pin "P$4") (pinfunction "4_P$4") (pintype "passive"))
    )
    (net (code "11") (name "CAN2_RXD") (class "Default")
      (node (ref "IC1") (pin "4") (pinfunction "RXD_4") (pintype "output"))
      (node (ref "PROZ1") (pin "50") (pinfunction "PB12_50") (pintype "bidirectional"))
    )
    (net (code "12") (name "CAN2_TXD") (class "Default")
      (node (ref "IC1") (pin "1") (pinfunction "TXD_1") (pintype "input"))
      (node (ref "PROZ1") (pin "49") (pinfunction "PB13_49") (pintype "bidirectional"))
    )
    (net (code "13") (name "CANP_H") (class "Default")
      (node (ref "D4") (pin "1") (pinfunction "P$1_1") (pintype "passive"))
      (node (ref "IC2") (pin "7") (pinfunction "CANH_7") (pintype "bidirectional"))
      (node (ref "L2") (pin "P$2") (pinfunction "2_P$2") (pintype "passive"))
      (node (ref "PROZ1") (pin "31") (pinfunction "CANH_31") (pintype "bidirectional"))
    )
    (net (code "14") (name "CANP_L") (class "Default")
      (node (ref "D4") (pin "2") (pinfunction "P$2_2") (pintype "passive"))
      (node (ref "IC2") (pin "6") (pinfunction "CANL_6") (pintype "bidirectional"))
      (node (ref "L2") (pin "P$4") (pinfunction "4_P$4") (pintype "passive"))
      (node (ref "PROZ1") (pin "32") (pinfunction "CANL_32") (pintype "bidirectional"))
    )
    (net (code "15") (name "CH_DI3_EX") (class "Default")
      (node (ref "Q9") (pin "3") (pinfunction "D_3") (pintype "passive"))
      (node (ref "R43") (pin "1") (pinfunction "1_1") (pintype "passive"))
      (node (ref "X18") (pin "3") (pinfunction "3_3") (pintype "passive"))
    )
    (net (code "16") (name "CH_DI4_EX") (class "Default")
      (node (ref "Q8") (pin "3") (pinfunction "D_3") (pintype "passive"))
      (node (ref "R42") (pin "1") (pinfunction "1_1") (pintype "passive"))
      (node (ref "X18") (pin "4") (pinfunction "4_4") (pintype "passive"))
    )
    (net (code "17") (name "CH_DO2_EX") (class "Default")
      (node (ref "R36") (pin "2") (pinfunction "2_2") (pintype "passive"))
      (node (ref "X18") (pin "6") (pinfunction "6_6") (pintype "passive"))
    )
    (net (code "18") (name "CH_FLT_EX") (class "Default")
      (node (ref "R37") (pin "2") (pinfunction "2_2") (pintype "passive"))
      (node (ref "X18") (pin "5") (pinfunction "5_5") (pintype "passive"))
    )
    (net (code "19") (name "CH_NDI3") (class "Default")
      (node (ref "PROZ1") (pin "7") (pinfunction "PA0_7") (pintype "bidirectional"))
      (node (ref "R40") (pin "2") (pinfunction "2_2") (pintype "passive"))
    )
    (net (code "20") (name "CH_NDI4") (class "Default")
      (node (ref "PROZ1") (pin "5") (pinfunction "PA1_5") (pintype "bidirectional"))
      (node (ref "R39") (pin "2") (pinfunction "2_2") (pintype "passive"))
    )
    (net (code "21") (name "CH_NDO2") (class "Default")
      (node (ref "PROZ1") (pin "19") (pinfunction "PC15_19") (pintype "bidirectional"))
      (node (ref "Q6") (pin "3") (pinfunction "D_3") (pintype "passive"))
      (node (ref "R34") (pin "1") (pinfunction "1_1") (pintype "passive"))
    )
    (net (code "22") (name "CH_NFLT") (class "Default")
      (node (ref "PROZ1") (pin "3") (pinfunction "PA2_3") (pintype "bidirectional"))
      (node (ref "Q7") (pin "3") (pinfunction "D_3") (pintype "passive"))
      (node (ref "R35") (pin "1") (pinfunction "1_1") (pintype "passive"))
    )
    (net (code "23") (name "CH_PON") (class "Default")
      (node (ref "PROZ1") (pin "9") (pinfunction "PC3_9") (pintype "bidirectional"))
      (node (ref "R38") (pin "1") (pinfunction "1_1") (pintype "passive"))
      (node (ref "R41") (pin "2") (pinfunction "2_2") (pintype "passive"))
    )
    (net (code "24") (name "CH_PON_EX") (class "Default")
      (node (ref "IC12") (pin "P$4") (pinfunction "D_P$4") (pintype "passive"))
      (node (ref "X18") (pin "2") (pinfunction "2_2") (pintype "passive"))
    )
    (net (code "25") (name "CS_B0") (class "Default")
      (node (ref "IC3") (pin "1") (pinfunction "A_1") (pintype "input"))
      (node (ref "PROZ1") (pin "43") (pinfunction "PA4_43") (pintype "bidirectional"))
    )
    (net (code "26") (name "CS_B1") (class "Default")
      (node (ref "IC3") (pin "2") (pinfunction "B_2") (pintype "input"))
      (node (ref "PROZ1") (pin "51") (pinfunction "PB15_51") (pintype "bidirectional"))
    )
    (net (code "27") (name "CS_B2") (class "Default")
      (node (ref "IC3") (pin "3") (pinfunction "C_3") (pintype "input"))
      (node (ref "PROZ1") (pin "52") (pinfunction "PC6_52") (pintype "bidirectional"))
    )
    (net (code "28") (name "GND") (class "Default")
      (node (ref "C1") (pin "2") (pinfunction "2_2") (pintype "passive"))
      (node (ref "C10") (pin "2") (pinfunction "2_2") (pintype "passive"))
      (node (ref "C11") (pin "2") (pinfunction "2_2") (pintype "passive"))
      (node (ref "C12") (pin "2") (pinfunction "2_2") (pintype "passive"))
      (node (ref "C13") (pin "2") (pinfunction "2_2") (pintype "passive"))
      (node (ref "C14") (pin "2") (pinfunction "2_2") (pintype "passive"))
      (node (ref "C15") (pin "2") (pinfunction "2_2") (pintype "passive"))
      (node (ref "C16") (pin "2") (pinfunction "2_2") (pintype "passive"))
      (node (ref "C17") (pin "2") (pinfunction "2_2") (pintype "passive"))
      (node (ref "C18") (pin "2") (pinfunction "2_2") (pintype "passive"))
      (node (ref "C19") (pin "2") (pinfunction "2_2") (pintype "passive"))
      (node (ref "C2") (pin "2") (pinfunction "2_2") (pintype "passive"))
      (node (ref "C22") (pin "2") (pinfunction "2_2") (pintype "passive"))
      (node (ref "C24") (pin "2") (pinfunction "2_2") (pintype "passive"))
      (node (ref "C3") (pin "2") (pinfunction "2_2") (pintype "passive"))
      (node (ref "C4") (pin "2") (pinfunction "2_2") (pintype "passive"))
      (node (ref "C5") (pin "2") (pinfunction "2_2") (pintype "passive"))
      (node (ref "C6") (pin "2") (pinfunction "2_2") (pintype "passive"))
      (node (ref "C8") (pin "2") (pinfunction "2_2") (pintype "passive"))
      (node (ref "C9") (pin "2") (pinfunction "2_2") (pintype "passive"))
      (node (ref "D1") (pin "A") (pinfunction "A_A") (pintype "passive"))
      (node (ref "D10") (pin "P$1") (pinfunction "P$1_P$1") (pintype "bidirectional"))
      (node (ref "D10") (pin "P$11") (pinfunction "P$1_P$11") (pintype "bidirectional"))
      (node (ref "D11") (pin "P$1") (pinfunction "P$1_P$1") (pintype "bidirectional"))
      (node (ref "D11") (pin "P$11") (pinfunction "P$1_P$11") (pintype "bidirectional"))
      (node (ref "D12") (pin "P$1") (pinfunction "P$1_P$1") (pintype "bidirectional"))
      (node (ref "D12") (pin "P$11") (pinfunction "P$1_P$11") (pintype "bidirectional"))
      (node (ref "D13") (pin "P$1") (pinfunction "P$1_P$1") (pintype "bidirectional"))
      (node (ref "D13") (pin "P$11") (pinfunction "P$1_P$11") (pintype "bidirectional"))
      (node (ref "D2") (pin "A") (pinfunction "A_A") (pintype "passive"))
      (node (ref "D3") (pin "3") (pinfunction "P$3_3") (pintype "passive"))
      (node (ref "D4") (pin "3") (pinfunction "P$3_3") (pintype "passive"))
      (node (ref "D5") (pin "P$1") (pinfunction "P$1_P$1") (pintype "bidirectional"))
      (node (ref "D5") (pin "P$11") (pinfunction "P$1_P$11") (pintype "bidirectional"))
      (node (ref "D6") (pin "P$1") (pinfunction "P$1_P$1") (pintype "bidirectional"))
      (node (ref "D6") (pin "P$11") (pinfunction "P$1_P$11") (pintype "bidirectional"))
      (node (ref "D7") (pin "P$1") (pinfunction "P$1_P$1") (pintype "bidirectional"))
      (node (ref "D7") (pin "P$11") (pinfunction "P$1_P$11") (pintype "bidirectional"))
      (node (ref "D8") (pin "P$1") (pinfunction "P$1_P$1") (pintype "bidirectional"))
      (node (ref "D8") (pin "P$11") (pinfunction "P$1_P$11") (pintype "bidirectional"))
      (node (ref "D9") (pin "P$1") (pinfunction "P$1_P$1") (pintype "bidirectional"))
      (node (ref "D9") (pin "P$11") (pinfunction "P$1_P$11") (pintype "bidirectional"))
      (node (ref "IC1") (pin "2") (pinfunction "GND_2") (pintype "power_in"))
      (node (ref "IC10") (pin "2") (pinfunction "GND_2") (pintype "bidirectional"))
      (node (ref "IC11") (pin "4") (pinfunction "GND_4") (pintype "power_in"))
      (node (ref "IC12") (pin "P$5") (pinfunction "S_P$5") (pintype "passive"))
      (node (ref "IC13") (pin "10") (pinfunction "GND_10") (pintype "bidirectional"))
      (node (ref "IC13") (pin "11") (pinfunction "GND_11") (pintype "bidirectional"))
      (node (ref "IC13") (pin "12") (pinfunction "GND_12") (pintype "bidirectional"))
      (node (ref "IC13") (pin "3") (pinfunction "GND_3") (pintype "bidirectional"))
      (node (ref "IC13") (pin "4") (pinfunction "GND_4") (pintype "bidirectional"))
      (node (ref "IC13") (pin "5") (pinfunction "GND_5") (pintype "bidirectional"))
      (node (ref "IC15") (pin "12") (pinfunction "GND2_12") (pintype "bidirectional"))
      (node (ref "IC15") (pin "13") (pinfunction "HEAT_13") (pintype "bidirectional"))
      (node (ref "IC15") (pin "6") (pinfunction "GND1_6") (pintype "bidirectional"))
      (node (ref "IC2") (pin "2") (pinfunction "GND_2") (pintype "power_in"))
      (node (ref "IC3") (pin "4") (pinfunction "G2A_4") (pintype "input"))
      (node (ref "IC3") (pin "5") (pinfunction "G2B_5") (pintype "input"))
      (node (ref "IC3") (pin "8") (pinfunction "GND_8") (pintype "power_in"))
      (node (ref "IC4") (pin "7") (pinfunction "VSS_7") (pintype "power_in"))
      (node (ref "IC6") (pin "12") (pinfunction "GND2_12") (pintype "bidirectional"))
      (node (ref "IC6") (pin "13") (pinfunction "HEAT_13") (pintype "bidirectional"))
      (node (ref "IC6") (pin "6") (pinfunction "GND1_6") (pintype "bidirectional"))
      (node (ref "IC7") (pin "12") (pinfunction "GND2_12") (pintype "bidirectional"))
      (node (ref "IC7") (pin "13") (pinfunction "HEAT_13") (pintype "bidirectional"))
      (node (ref "IC7") (pin "6") (pinfunction "GND1_6") (pintype "bidirectional"))
      (node (ref "IC8") (pin "2") (pinfunction "GND_2") (pintype "bidirectional"))
      (node (ref "IC9") (pin "2") (pinfunction "GND_2") (pintype "bidirectional"))
      (node (ref "JP1") (pin "3") (pinfunction "3_3") (pintype "passive"))
      (node (ref "JP2") (pin "3") (pinfunction "3_3") (pintype "passive"))
      (node (ref "PROZ1") (pin "47") (pinfunction "GND_47") (pintype "passive"))
      (node (ref "PROZ1") (pin "48") (pinfunction "GND_48") (pintype "passive"))
      (node (ref "Q1") (pin "2") (pinfunction "S_2") (pintype "passive"))
      (node (ref "Q12") (pin "2") (pinfunction "S_2") (pintype "passive"))
      (node (ref "Q13") (pin "2") (pinfunction "S_2") (pintype "passive"))
      (node (ref "Q2") (pin "2") (pinfunction "S_2") (pintype "passive"))
      (node (ref "Q3") (pin "2") (pinfunction "S_2") (pintype "passive"))
      (node (ref "Q4") (pin "2") (pinfunction "S_2") (pintype "passive"))
      (node (ref "Q5") (pin "2") (pinfunction "S_2") (pintype "passive"))
      (node (ref "Q6") (pin "2") (pinfunction "S_2") (pintype "passive"))
      (node (ref "Q7") (pin "2") (pinfunction "S_2") (pintype "passive"))
      (node (ref "Q8") (pin "2") (pinfunction "S_2") (pintype "passive"))
      (node (ref "Q9") (pin "2") (pinfunction "S_2") (pintype "passive"))
      (node (ref "R1") (pin "1") (pinfunction "1_1") (pintype "passive"))
      (node (ref "R11") (pin "1") (pinfunction "1_1") (pintype "passive"))
      (node (ref "R12") (pin "1") (pinfunction "1_1") (pintype "passive"))
      (node (ref "R13") (pin "1") (pinfunction "1_1") (pintype "passive"))
      (node (ref "R14") (pin "1") (pinfunction "1_1") (pintype "passive"))
      (node (ref "R16") (pin "1") (pinfunction "1_1") (pintype "passive"))
      (node (ref "R17") (pin "1") (pinfunction "1_1") (pintype "passive"))
      (node (ref "R2") (pin "1") (pinfunction "1_1") (pintype "passive"))
      (node (ref "R20") (pin "1") (pinfunction "1_1") (pintype "passive"))
      (node (ref "R23") (pin "1") (pinfunction "1_1") (pintype "passive"))
      (node (ref "R27") (pin "2") (pinfunction "2_2") (pintype "passive"))
      (node (ref "R29") (pin "2") (pinfunction "2_2") (pintype "passive"))
      (node (ref "R3") (pin "1") (pinfunction "1_1") (pintype "passive"))
      (node (ref "R33") (pin "1") (pinfunction "1_1") (pintype "passive"))
      (node (ref "R38") (pin "2") (pinfunction "2_2") (pintype "passive"))
      (node (ref "R4") (pin "1") (pinfunction "1_1") (pintype "passive"))
      (node (ref "R50") (pin "1") (pinfunction "1_1") (pintype "passive"))
      (node (ref "R51") (pin "1") (pinfunction "1_1") (pintype "passive"))
      (node (ref "R52") (pin "1") (pinfunction "1_1") (pintype "passive"))
      (node (ref "R53") (pin "1") (pinfunction "1_1") (pintype "passive"))
      (node (ref "R54") (pin "1") (pinfunction "1_1") (pintype "passive"))
      (node (ref "R55") (pin "1") (pinfunction "1_1") (pintype "passive"))
      (node (ref "R56") (pin "2") (pinfunction "2_2") (pintype "passive"))
      (node (ref "R57") (pin "2") (pinfunction "2_2") (pintype "passive"))
      (node (ref "R58") (pin "2") (pinfunction "2_2") (pintype "passive"))
      (node (ref "R63") (pin "1") (pinfunction "1_1") (pintype "passive"))
      (node (ref "R77") (pin "1") (pinfunction "1_1") (pintype "passive"))
      (node (ref "R78") (pin "1") (pinfunction "1_1") (pintype "passive"))
      (node (ref "R9") (pin "1") (pinfunction "1_1") (pintype "passive"))
      (node (ref "TB1") (pin "GND") (pinfunction "GND_GND") (pintype "power_in"))
      (node (ref "TB1") (pin "GND2") (pinfunction "GND_GND2") (pintype "power_in"))
      (node (ref "TERA-DC/DC1") (pin "GND@1") (pinfunction "GND_GND@1") (pintype "power_in"))
      (node (ref "TERA-DC/DC1") (pin "GND@2") (pinfunction "GND_GND@2") (pintype "power_in"))
      (node (ref "X1") (pin "1") (pinfunction "1_1") (pintype "passive"))
      (node (ref "X13") (pin "1") (pinfunction "1_1") (pintype "passive"))
      (node (ref "X14") (pin "1") (pinfunction "1_1") (pintype "passive"))
      (node (ref "X15") (pin "1") (pinfunction "1_1") (pintype "passive"))
      (node (ref "X18") (pin "1") (pinfunction "1_1") (pintype "passive"))
      (node (ref "X2") (pin "1") (pinfunction "GND_1") (pintype "passive"))
      (node (ref "X20") (pin "P$1") (pinfunction "1_P$1") (pintype "bidirectional"))
      (node (ref "X3") (pin "1") (pinfunction "GND_1") (pintype "passive"))
      (node (ref "X4") (pin "1") (pinfunction "GND_1") (pintype "passive"))
      (node (ref "X5") (pin "P$1") (pinfunction "1_P$1") (pintype "bidirectional"))
    )
    (net (code "29") (name "HS_CO1") (class "Default")
      (node (ref "IC7") (pin "4") (pinfunction "CO1_4") (pintype "bidirectional"))
      (node (ref "PROZ1") (pin "36") (pinfunction "PB2_36") (pintype "bidirectional"))
    )
    (net (code "30") (name "HS_RM") (class "Default")
      (node (ref "PROZ1") (pin "37") (pinfunction "PB1_37") (pintype "bidirectional"))
      (node (ref "Q4") (pin "3") (pinfunction "D_3") (pintype "passive"))
      (node (ref "R21") (pin "1") (pinfunction "1_1") (pintype "passive"))
    )
    (net (code "31") (name "HS_RM_EX") (class "Default")
      (node (ref "R22") (pin "2") (pinfunction "2_2") (pintype "passive"))
      (node (ref "R23") (pin "2") (pinfunction "2_2") (pintype "passive"))
      (node (ref "X11") (pin "P$3") (pinfunction "3_P$3") (pintype "bidirectional"))
    )
    (net (code "32") (name "IL1") (class "Default")
      (node (ref "PROZ1") (pin "14") (pinfunction "PB6_14") (pintype "bidirectional"))
      (node (ref "Q1") (pin "1") (pinfunction "G_1") (pintype "passive"))
      (node (ref "R9") (pin "2") (pinfunction "2_2") (pintype "passive"))
    )
    (net (code "33") (name "IL2") (class "Default")
      (node (ref "PROZ1") (pin "12") (pinfunction "PB7_12") (pintype "bidirectional"))
      (node (ref "Q2") (pin "1") (pinfunction "G_1") (pintype "passive"))
      (node (ref "R13") (pin "2") (pinfunction "2_2") (pintype "passive"))
    )
    (net (code "34") (name "ILK1") (class "Default")
      (node (ref "IC4") (pin "11") (pinfunction "I0_11") (pintype "input"))
      (node (ref "JP4") (pin "2") (pinfunction "2_2") (pintype "passive"))
      (node (ref "Q1") (pin "3") (pinfunction "D_3") (pintype "passive"))
      (node (ref "SJ1") (pin "2") (pinfunction "2_2") (pintype "passive"))
      (node (ref "X18") (pin "8") (pinfunction "8_8") (pintype "passive"))
    )
    (net (code "35") (name "ILK1_CH") (class "Default")
      (node (ref "SJ1") (pin "1") (pinfunction "1_1") (pintype "passive"))
      (node (ref "X18") (pin "7") (pinfunction "7_7") (pintype "passive"))
      (node (ref "X20") (pin "P$3") (pinfunction "3_P$3") (pintype "bidirectional"))
    )
    (net (code "36") (name "ILK2") (class "Default")
      (node (ref "IC4") (pin "12") (pinfunction "I1_12") (pintype "input"))
      (node (ref "IC4") (pin "13") (pinfunction "I2_13") (pintype "input"))
      (node (ref "JP3") (pin "2") (pinfunction "2_2") (pintype "passive"))
      (node (ref "Q2") (pin "3") (pinfunction "D_3") (pintype "passive"))
      (node (ref "X20") (pin "P$2") (pinfunction "2_P$2") (pintype "bidirectional"))
    )
    (net (code "37") (name "INTERLOCK_OK") (class "Default")
      (node (ref "IC4") (pin "10") (pinfunction "O_10") (pintype "output"))
      (node (ref "IC6") (pin "1") (pinfunction "IN2_1") (pintype "bidirectional"))
      (node (ref "IC6") (pin "7") (pinfunction "IN1_7") (pintype "bidirectional"))
      (node (ref "IC7") (pin "1") (pinfunction "IN2_1") (pintype "bidirectional"))
      (node (ref "IC7") (pin "7") (pinfunction "IN1_7") (pintype "bidirectional"))
      (node (ref "LED5") (pin "A") (pinfunction "A_A") (pintype "passive"))
      (node (ref "PROZ1") (pin "44") (pinfunction "PA3_44") (pintype "bidirectional"))
    )
    (net (code "38") (name "JTCK") (class "Default")
      (node (ref "PROZ1") (pin "18") (pinfunction "PA14_18") (pintype "bidirectional"))
      (node (ref "X2") (pin "5") (pinfunction "JTCK_5") (pintype "passive"))
    )
    (net (code "39") (name "JTDI") (class "Default")
      (node (ref "PROZ1") (pin "16") (pinfunction "PA15_16") (pintype "bidirectional"))
      (node (ref "X2") (pin "6") (pinfunction "JTDI_6") (pintype "passive"))
    )
    (net (code "40") (name "JTDO") (class "Default")
      (node (ref "PROZ1") (pin "20") (pinfunction "PB3_20") (pintype "bidirectional"))
      (node (ref "X2") (pin "7") (pinfunction "JTDO_7") (pintype "passive"))
    )
    (net (code "41") (name "JTMS") (class "Default")
      (node (ref "PROZ1") (pin "59") (pinfunction "PA13_59") (pintype "bidirectional"))
      (node (ref "X2") (pin "3") (pinfunction "JTMS_3") (pintype "passive"))
    )
    (net (code "42") (name "JTNRST") (class "Default")
      (node (ref "PROZ1") (pin "22") (pinfunction "PB4_22") (pintype "bidirectional"))
      (node (ref "X2") (pin "8") (pinfunction "JTNRST_8") (pintype "passive"))
    )
    (net (code "43") (name "LED1") (class "Default")
      (node (ref "PROZ1") (pin "25") (pinfunction "PB5_25") (pintype "bidirectional"))
    )
    (net (code "44") (name "LED2") (class "Default")
      (node (ref "PROZ1") (pin "27") (pinfunction "PD2_27") (pintype "bidirectional"))
    )
    (net (code "45") (name "LED3") (class "Default")
      (node (ref "PROZ1") (pin "29") (pinfunction "PC12_29") (pintype "bidirectional"))
    )
    (net (code "46") (name "LEM_1") (class "Default")
      (node (ref "C18") (pin "1") (pinfunction "1_1") (pintype "passive"))
      (node (ref "D7") (pin "P$2") (pinfunction "P$2_P$2") (pintype "bidirectional"))
      (node (ref "PROZ1") (pin "15") (pinfunction "PC0_15") (pintype "bidirectional"))
      (node (ref "R26") (pin "2") (pinfunction "2_2") (pintype "passive"))
    )
    (net (code "47") (name "LEM_2") (class "Default")
      (node (ref "C17") (pin "1") (pinfunction "1_1") (pintype "passive"))
      (node (ref "D6") (pin "P$2") (pinfunction "P$2_P$2") (pintype "bidirectional"))
      (node (ref "PROZ1") (pin "13") (pinfunction "PC1_13") (pintype "bidirectional"))
      (node (ref "R25") (pin "2") (pinfunction "2_2") (pintype "passive"))
    )
    (net (code "48") (name "LEM_3") (class "Default")
      (node (ref "C16") (pin "1") (pinfunction "1_1") (pintype "passive"))
      (node (ref "D8") (pin "P$2") (pinfunction "P$2_P$2") (pintype "bidirectional"))
      (node (ref "PROZ1") (pin "11") (pinfunction "PC2_11") (pintype "bidirectional"))
      (node (ref "R24") (pin "2") (pinfunction "2_2") (pintype "passive"))
    )
    (net (code "49") (name "LK_1") (class "Default")
      (node (ref "IC13") (pin "9") (pinfunction "IN1_9") (pintype "bidirectional"))
      (node (ref "PROZ1") (pin "23") (pinfunction "PC13_23") (pintype "bidirectional"))
    )
    (net (code "50") (name "LK_2") (class "Default")
      (node (ref "IC13") (pin "6") (pinfunction "IN2_6") (pintype "bidirectional"))
      (node (ref "PROZ1") (pin "21") (pinfunction "PC14_21") (pintype "bidirectional"))
    )
    (net (code "51") (name "LK_EF") (class "Default")
      (node (ref "IC13") (pin "8") (pinfunction "EF_8") (pintype "bidirectional"))
      (node (ref "PROZ1") (pin "8") (pinfunction "PB9_8") (pintype "bidirectional"))
      (node (ref "R46") (pin "1") (pinfunction "1_1") (pintype "passive"))
    )
    (net (code "52") (name "LK_ON") (class "Default")
      (node (ref "IC13") (pin "7") (pinfunction "INH_7") (pintype "bidirectional"))
      (node (ref "PROZ1") (pin "10") (pinfunction "PB8_10") (pintype "bidirectional"))
    )
    (net (code "53") (name "LK_RM") (class "Default")
      (node (ref "PROZ1") (pin "58") (pinfunction "PA10_58") (pintype "bidirectional"))
      (node (ref "Q5") (pin "3") (pinfunction "D_3") (pintype "passive"))
      (node (ref "R31") (pin "1") (pinfunction "1_1") (pintype "passive"))
    )
    (net (code "54") (name "MISO") (class "Default")
      (node (ref "IC15") (pin "11") (pinfunction "MISO/ST2_11") (pintype "bidirectional"))
      (node (ref "IC6") (pin "11") (pinfunction "MISO/ST2_11") (pintype "bidirectional"))
      (node (ref "IC7") (pin "11") (pinfunction "MISO/ST2_11") (pintype "bidirectional"))
      (node (ref "R48") (pin "2") (pinfunction "2_2") (pintype "passive"))
      (node (ref "X5") (pin "P$6") (pinfunction "6_P$6") (pintype "bidirectional"))
    )
    (net (code "55") (name "MISO_S") (class "Default")
      (node (ref "D12") (pin "P$2") (pinfunction "P$2_P$2") (pintype "bidirectional"))
      (node (ref "PROZ1") (pin "42") (pinfunction "PA6_42") (pintype "bidirectional"))
      (node (ref "R48") (pin "1") (pinfunction "1_1") (pintype "passive"))
    )
    (net (code "56") (name "MOSI") (class "Default")
      (node (ref "IC15") (pin "2") (pinfunction "MOSI_2") (pintype "bidirectional"))
      (node (ref "IC6") (pin "2") (pinfunction "MOSI_2") (pintype "bidirectional"))
      (node (ref "IC7") (pin "2") (pinfunction "MOSI_2") (pintype "bidirectional"))
      (node (ref "R49") (pin "2") (pinfunction "2_2") (pintype "passive"))
      (node (ref "X5") (pin "P$5") (pinfunction "5_P$5") (pintype "bidirectional"))
    )
    (net (code "57") (name "MOSI_S") (class "Default")
      (node (ref "D13") (pin "P$2") (pinfunction "P$2_P$2") (pintype "bidirectional"))
      (node (ref "PROZ1") (pin "41") (pinfunction "PA7_41") (pintype "bidirectional"))
      (node (ref "R49") (pin "1") (pinfunction "1_1") (pintype "passive"))
    )
    (net (code "58") (name "NALERT") (class "Default")
      (node (ref "IC4") (pin "9") (pinfunction "O_9") (pintype "output"))
      (node (ref "LED4") (pin "A") (pinfunction "A_A") (pintype "passive"))
      (node (ref "PROZ1") (pin "35") (pinfunction "PB10_35") (pintype "bidirectional"))
    )
    (net (code "59") (name "NALERT1") (class "Default")
      (node (ref "IC4") (pin "1") (pinfunction "I0_1") (pintype "input"))
      (node (ref "R50") (pin "2") (pinfunction "2_2") (pintype "passive"))
      (node (ref "X6") (pin "P$2") (pinfunction "2_P$2") (pintype "bidirectional"))
    )
    (net (code "60") (name "NALERT2") (class "Default")
      (node (ref "IC4") (pin "2") (pinfunction "I1_2") (pintype "input"))
      (node (ref "R51") (pin "2") (pinfunction "2_2") (pintype "passive"))
      (node (ref "X7") (pin "P$2") (pinfunction "2_P$2") (pintype "bidirectional"))
    )
    (net (code "61") (name "NALERT3") (class "Default")
      (node (ref "IC4") (pin "8") (pinfunction "I2_8") (pintype "input"))
      (node (ref "R52") (pin "2") (pinfunction "2_2") (pintype "passive"))
      (node (ref "X8") (pin "P$2") (pinfunction "2_P$2") (pintype "bidirectional"))
    )
    (net (code "62") (name "NCS1") (class "Default")
      (node (ref "IC3") (pin "15") (pinfunction "Y0_15") (pintype "output"))
      (node (ref "X5") (pin "P$4") (pinfunction "4_P$4") (pintype "bidirectional"))
    )
    (net (code "63") (name "NCS2") (class "Default")
      (node (ref "IC3") (pin "14") (pinfunction "Y1_14") (pintype "output"))
      (node (ref "X5") (pin "P$3") (pinfunction "3_P$3") (pintype "bidirectional"))
    )
    (net (code "64") (name "NCS3") (class "Default")
      (node (ref "IC3") (pin "13") (pinfunction "Y2_13") (pintype "output"))
      (node (ref "X5") (pin "P$2") (pinfunction "2_P$2") (pintype "bidirectional"))
    )
    (net (code "65") (name "NCS4") (class "Default")
      (node (ref "IC3") (pin "12") (pinfunction "Y3_12") (pintype "output"))
      (node (ref "IC7") (pin "8") (pinfunction "NCS_8") (pintype "bidirectional"))
    )
    (net (code "66") (name "NCS5") (class "Default")
      (node (ref "IC3") (pin "11") (pinfunction "Y4_11") (pintype "output"))
      (node (ref "IC6") (pin "8") (pinfunction "NCS_8") (pintype "bidirectional"))
    )
    (net (code "67") (name "NCS6") (class "Default")
      (node (ref "IC15") (pin "8") (pinfunction "NCS_8") (pintype "bidirectional"))
      (node (ref "IC3") (pin "10") (pinfunction "Y5_10") (pintype "output"))
    )
    (net (code "68") (name "NCS7") (class "Default")
      (node (ref "IC3") (pin "9") (pinfunction "Y6_9") (pintype "output"))
    )
    (net (code "69") (name "NCS8") (class "Default")
      (node (ref "IC3") (pin "7") (pinfunction "Y7_7") (pintype "output"))
    )
    (net (code "70") (name "NFAULT") (class "Default")
      (node (ref "IC4") (pin "6") (pinfunction "O_6") (pintype "output"))
      (node (ref "LED3") (pin "A") (pinfunction "A_A") (pintype "passive"))
      (node (ref "PROZ1") (pin "53") (pinfunction "PC7_53") (pintype "bidirectional"))
    )
    (net (code "71") (name "NFAULT1") (class "Default")
      (node (ref "IC4") (pin "3") (pinfunction "I0_3") (pintype "input"))
      (node (ref "R53") (pin "2") (pinfunction "2_2") (pintype "passive"))
      (node (ref "X6") (pin "P$1") (pinfunction "1_P$1") (pintype "bidirectional"))
    )
    (net (code "72") (name "NFAULT2") (class "Default")
      (node (ref "IC4") (pin "4") (pinfunction "I1_4") (pintype "input"))
      (node (ref "R54") (pin "2") (pinfunction "2_2") (pintype "passive"))
      (node (ref "X7") (pin "P$1") (pinfunction "1_P$1") (pintype "bidirectional"))
    )
    (net (code "73") (name "NFAULT3") (class "Default")
      (node (ref "IC4") (pin "5") (pinfunction "I2_5") (pintype "input"))
      (node (ref "R55") (pin "2") (pinfunction "2_2") (pintype "passive"))
      (node (ref "X8") (pin "P$1") (pinfunction "1_P$1") (pintype "bidirectional"))
    )
    (net (code "74") (name "NRST") (class "Default")
      (node (ref "PROZ1") (pin "17") (pinfunction "NRST_17") (pintype "bidirectional"))
      (node (ref "X2") (pin "4") (pinfunction "NRST_4") (pintype "passive"))
    )
    (net (code "75") (name "Net-(C4-Pad1)") (class "Default")
      (node (ref "C4") (pin "1") (pinfunction "1_1") (pintype "passive"))
      (node (ref "R5") (pin "1") (pinfunction "1_1") (pintype "passive"))
      (node (ref "R6") (pin "1") (pinfunction "1_1") (pintype "passive"))
    )
    (net (code "76") (name "Net-(C5-Pad1)") (class "Default")
      (node (ref "C5") (pin "1") (pinfunction "1_1") (pintype "passive"))
      (node (ref "R7") (pin "1") (pinfunction "1_1") (pintype "passive"))
      (node (ref "R8") (pin "1") (pinfunction "1_1") (pintype "passive"))
    )
    (net (code "77") (name "Net-(IC1-RS)") (class "Default")
      (node (ref "IC1") (pin "8") (pinfunction "RS_8") (pintype "passive"))
      (node (ref "R3") (pin "2") (pinfunction "2_2") (pintype "passive"))
    )
    (net (code "78") (name "Net-(IC2-RS)") (class "Default")
      (node (ref "IC2") (pin "8") (pinfunction "RS_8") (pintype "passive"))
      (node (ref "R4") (pin "2") (pinfunction "2_2") (pintype "passive"))
    )
    (net (code "79") (name "Net-(IC2-VCC)") (class "Default")
      (node (ref "C2") (pin "1") (pinfunction "1_1") (pintype "passive"))
      (node (ref "IC2") (pin "3") (pinfunction "VCC_3") (pintype "power_in"))
      (node (ref "J3") (pin "P$2") (pinfunction "P$2_P$2") (pintype "bidirectional"))
    )
    (net (code "80") (name "Net-(IC6-OUT1)") (class "Default")
      (node (ref "IC6") (pin "9") (pinfunction "OUT1_9") (pintype "bidirectional"))
      (node (ref "R61") (pin "1") (pinfunction "1_1") (pintype "passive"))
      (node (ref "X10") (pin "P$1") (pinfunction "1_P$1") (pintype "bidirectional"))
    )
    (net (code "81") (name "Net-(IC6-OUT2)") (class "Default")
      (node (ref "IC6") (pin "3") (pinfunction "OUT2_3") (pintype "bidirectional"))
      (node (ref "R62") (pin "1") (pinfunction "1_1") (pintype "passive"))
      (node (ref "X9") (pin "P$1") (pinfunction "1_P$1") (pintype "bidirectional"))
    )
    (net (code "82") (name "Net-(IC7-OUT1)") (class "Default")
      (node (ref "IC7") (pin "9") (pinfunction "OUT1_9") (pintype "bidirectional"))
      (node (ref "R59") (pin "1") (pinfunction "1_1") (pintype "passive"))
      (node (ref "X12") (pin "P$1") (pinfunction "1_P$1") (pintype "bidirectional"))
    )
    (net (code "83") (name "Net-(IC7-OUT2)") (class "Default")
      (node (ref "IC7") (pin "3") (pinfunction "OUT2_3") (pintype "bidirectional"))
      (node (ref "R60") (pin "1") (pinfunction "1_1") (pintype "passive"))
      (node (ref "X11") (pin "P$1") (pinfunction "1_P$1") (pintype "bidirectional"))
    )
    (net (code "84") (name "Net-(IC8-VREF)") (class "Default")
      (node (ref "C13") (pin "1") (pinfunction "1_1") (pintype "passive"))
      (node (ref "IC8") (pin "5") (pinfunction "VREF_5") (pintype "bidirectional"))
      (node (ref "R58") (pin "1") (pinfunction "1_1") (pintype "passive"))
      (node (ref "X13") (pin "3") (pinfunction "3_3") (pintype "passive"))
    )
    (net (code "85") (name "Net-(IC9-VREF)") (class "Default")
      (node (ref "C14") (pin "1") (pinfunction "1_1") (pintype "passive"))
      (node (ref "IC9") (pin "5") (pinfunction "VREF_5") (pintype "bidirectional"))
      (node (ref "R57") (pin "1") (pinfunction "1_1") (pintype "passive"))
      (node (ref "X14") (pin "3") (pinfunction "3_3") (pintype "passive"))
    )
    (net (code "86") (name "Net-(IC10-VREF)") (class "Default")
      (node (ref "C15") (pin "1") (pinfunction "1_1") (pintype "passive"))
      (node (ref "IC10") (pin "5") (pinfunction "VREF_5") (pintype "bidirectional"))
      (node (ref "R56") (pin "1") (pinfunction "1_1") (pintype "passive"))
      (node (ref "X15") (pin "3") (pinfunction "3_3") (pintype "passive"))
    )
    (net (code "87") (name "Net-(IC12A-D)") (class "Default")
      (node (ref "IC12") (pin "P$6") (pinfunction "D_P$6") (pintype "passive"))
      (node (ref "R44") (pin "1") (pinfunction "1_1") (pintype "passive"))
      (node (ref "R45") (pin "2") (pinfunction "2_2") (pintype "passive"))
    )
    (net (code "88") (name "Net-(IC12A-G)") (class "Default")
      (node (ref "IC12") (pin "P$1") (pinfunction "G_P$1") (pintype "passive"))
      (node (ref "R41") (pin "1") (pinfunction "1_1") (pintype "passive"))
    )
    (net (code "89") (name "Net-(IC12B-G)") (class "Default")
      (node (ref "IC12") (pin "P$3") (pinfunction "G_P$3") (pintype "passive"))
      (node (ref "R45") (pin "1") (pinfunction "1_1") (pintype "passive"))
    )
    (net (code "90") (name "Net-(IC13-OUT1)") (class "Default")
      (node (ref "IC13") (pin "13") (pinfunction "OUT1_13") (pintype "bidirectional"))
      (node (ref "X17") (pin "P$2") (pinfunction "2_P$2") (pintype "bidirectional"))
    )
    (net (code "91") (name "Net-(IC13-OUT2)") (class "Default")
      (node (ref "IC13") (pin "2") (pinfunction "OUT2_2") (pintype "bidirectional"))
      (node (ref "X17") (pin "P$1") (pinfunction "1_P$1") (pintype "bidirectional"))
    )
    (net (code "92") (name "Net-(IC15-IN1)") (class "Default")
      (node (ref "IC15") (pin "7") (pinfunction "IN1_7") (pintype "bidirectional"))
      (node (ref "JP1") (pin "2") (pinfunction "2_2") (pintype "passive"))
    )
    (net (code "93") (name "Net-(IC15-IN2)") (class "Default")
      (node (ref "IC15") (pin "1") (pinfunction "IN2_1") (pintype "bidirectional"))
      (node (ref "JP2") (pin "2") (pinfunction "2_2") (pintype "passive"))
    )
    (net (code "94") (name "Net-(IC15-OUT1)") (class "Default")
      (node (ref "IC15") (pin "9") (pinfunction "OUT1_9") (pintype "bidirectional"))
      (node (ref "R71") (pin "1") (pinfunction "1_1") (pintype "passive"))
      (node (ref "X21") (pin "P$1") (pinfunction "1_P$1") (pintype "bidirectional"))
    )
    (net (code "95") (name "Net-(IC15-OUT2)") (class "Default")
      (node (ref "IC15") (pin "3") (pinfunction "OUT2_3") (pintype "bidirectional"))
      (node (ref "R72") (pin "1") (pinfunction "1_1") (pintype "passive"))
      (node (ref "X22") (pin "P$1") (pinfunction "1_P$1") (pintype "bidirectional"))
    )
    (net (code "96") (name "Net-(J1-PadP$2)") (class "Default")
      (node (ref "J1") (pin "P$2") (pinfunction "P$2_P$2") (pintype "bidirectional"))
      (node (ref "R7") (pin "2") (pinfunction "2_2") (pintype "passive"))
    )
    (net (code "97") (name "Net-(J2-PadP$2)") (class "Default")
      (node (ref "J2") (pin "P$2") (pinfunction "P$2_P$2") (pintype "bidirectional"))
      (node (ref "R5") (pin "2") (pinfunction "2_2") (pintype "passive"))
    )
    (net (code "98") (name "Net-(JP3-Pad1)") (class "Default")
      (node (ref "JP3") (pin "1") (pinfunction "1_1") (pintype "passive"))
      (node (ref "R15") (pin "1") (pinfunction "1_1") (pintype "passive"))
    )
    (net (code "99") (name "Net-(JP3-Pad3)") (class "Default")
      (node (ref "JP3") (pin "3") (pinfunction "3_3") (pintype "passive"))
      (node (ref "R16") (pin "2") (pinfunction "2_2") (pintype "passive"))
    )
    (net (code "100") (name "Net-(JP4-Pad1)") (class "Default")
      (node (ref "JP4") (pin "1") (pinfunction "1_1") (pintype "passive"))
      (node (ref "R10") (pin "1") (pinfunction "1_1") (pintype "passive"))
    )
    (net (code "101") (name "Net-(JP4-Pad3)") (class "Default")
      (node (ref "JP4") (pin "3") (pinfunction "3_3") (pintype "passive"))
      (node (ref "R11") (pin "2") (pinfunction "2_2") (pintype "passive"))
    )
    (net (code "102") (name "Net-(LED1-PadC)") (class "Default")
      (node (ref "LED1") (pin "C") (pinfunction "C_C") (pintype "passive"))
      (node (ref "R1") (pin "2") (pinfunction "2_2") (pintype "passive"))
    )
    (net (code "103") (name "Net-(LED2-PadC)") (class "Default")
      (node (ref "LED2") (pin "C") (pinfunction "C_C") (pintype "passive"))
      (node (ref "R2") (pin "2") (pinfunction "2_2") (pintype "passive"))
    )
    (net (code "104") (name "Net-(LED3-PadC)") (class "Default")
      (node (ref "LED3") (pin "C") (pinfunction "C_C") (pintype "passive"))
      (node (ref "R12") (pin "2") (pinfunction "2_2") (pintype "passive"))
    )
    (net (code "105") (name "Net-(LED4-PadC)") (class "Default")
      (node (ref "LED4") (pin "C") (pinfunction "C_C") (pintype "passive"))
      (node (ref "R14") (pin "2") (pinfunction "2_2") (pintype "passive"))
    )
    (net (code "106") (name "Net-(LED5-PadC)") (class "Default")
      (node (ref "LED5") (pin "C") (pinfunction "C_C") (pintype "passive"))
      (node (ref "R17") (pin "2") (pinfunction "2_2") (pintype "passive"))
    )
    (net (code "107") (name "Net-(LED6-PadC)") (class "Default")
      (node (ref "LED6") (pin "C") (pinfunction "C_C") (pintype "passive"))
      (node (ref "R59") (pin "2") (pinfunction "2_2") (pintype "passive"))
    )
    (net (code "108") (name "Net-(LED7-PadC)") (class "Default")
      (node (ref "LED7") (pin "C") (pinfunction "C_C") (pintype "passive"))
      (node (ref "R60") (pin "2") (pinfunction "2_2") (pintype "passive"))
    )
    (net (code "109") (name "Net-(LED8-PadC)") (class "Default")
      (node (ref "LED8") (pin "C") (pinfunction "C_C") (pintype "passive"))
      (node (ref "R61") (pin "2") (pinfunction "2_2") (pintype "passive"))
    )
    (net (code "110") (name "Net-(LED9-PadC)") (class "Default")
      (node (ref "LED9") (pin "C") (pinfunction "C_C") (pintype "passive"))
      (node (ref "R62") (pin "2") (pinfunction "2_2") (pintype "passive"))
    )
    (net (code "111") (name "Net-(LED10-PadC)") (class "Default")
      (node (ref "LED10") (pin "C") (pinfunction "C_C") (pintype "passive"))
      (node (ref "R63") (pin "2") (pinfunction "2_2") (pintype "passive"))
    )
    (net (code "112") (name "Net-(LED12-PadC)") (class "Default")
      (node (ref "LED12") (pin "C") (pinfunction "C_C") (pintype "passive"))
      (node (ref "R71") (pin "2") (pinfunction "2_2") (pintype "passive"))
    )
    (net (code "113") (name "Net-(LED13-PadC)") (class "Default")
      (node (ref "LED13") (pin "C") (pinfunction "C_C") (pintype "passive"))
      (node (ref "R72") (pin "2") (pinfunction "2_2") (pintype "passive"))
    )
    (net (code "114") (name "Net-(Q3-G)") (class "Default")
      (node (ref "Q3") (pin "1") (pinfunction "G_1") (pintype "passive"))
      (node (ref "R19") (pin "1") (pinfunction "1_1") (pintype "passive"))
    )
    (net (code "115") (name "Net-(Q4-G)") (class "Default")
      (node (ref "Q4") (pin "1") (pinfunction "G_1") (pintype "passive"))
      (node (ref "R22") (pin "1") (pinfunction "1_1") (pintype "passive"))
    )
    (net (code "116") (name "Net-(Q5-G)") (class "Default")
      (node (ref "Q5") (pin "1") (pinfunction "G_1") (pintype "passive"))
      (node (ref "R32") (pin "1") (pinfunction "1_1") (pintype "passive"))
    )
    (net (code "117") (name "Net-(Q6-G)") (class "Default")
      (node (ref "Q6") (pin "1") (pinfunction "G_1") (pintype "passive"))
      (node (ref "R36") (pin "1") (pinfunction "1_1") (pintype "passive"))
    )
    (net (code "118") (name "Net-(Q7-G)") (class "Default")
      (node (ref "Q7") (pin "1") (pinfunction "G_1") (pintype "passive"))
      (node (ref "R37") (pin "1") (pinfunction "1_1") (pintype "passive"))
    )
    (net (code "119") (name "Net-(Q8-G)") (class "Default")
      (node (ref "Q8") (pin "1") (pinfunction "G_1") (pintype "passive"))
      (node (ref "R39") (pin "1") (pinfunction "1_1") (pintype "passive"))
    )
    (net (code "120") (name "Net-(Q9-G)") (class "Default")
      (node (ref "Q9") (pin "1") (pinfunction "G_1") (pintype "passive"))
      (node (ref "R40") (pin "1") (pinfunction "1_1") (pintype "passive"))
    )
    (net (code "121") (name "Net-(Q12-G)") (class "Default")
      (node (ref "Q12") (pin "1") (pinfunction "G_1") (pintype "passive"))
      (node (ref "R76") (pin "1") (pinfunction "1_1") (pintype "passive"))
    )
    (net (code "122") (name "Net-(Q13-G)") (class "Default")
      (node (ref "Q13") (pin "1") (pinfunction "G_1") (pintype "passive"))
      (node (ref "R74") (pin "1") (pinfunction "1_1") (pintype "passive"))
    )
    (net (code "123") (name "Net-(R24-Pad1)") (class "Default")
      (node (ref "R24") (pin "1") (pinfunction "1_1") (pintype "passive"))
      (node (ref "X13") (pin "2") (pinfunction "2_2") (pintype "passive"))
    )
    (net (code "124") (name "Net-(R25-Pad1)") (class "Default")
      (node (ref "R25") (pin "1") (pinfunction "1_1") (pintype "passive"))
      (node (ref "X14") (pin "2") (pinfunction "2_2") (pintype "passive"))
    )
    (net (code "125") (name "Net-(R26-Pad1)") (class "Default")
      (node (ref "R26") (pin "1") (pinfunction "1_1") (pintype "passive"))
      (node (ref "X15") (pin "2") (pinfunction "2_2") (pintype "passive"))
    )
    (net (code "126") (name "Net-(R28-Pad1)") (class "Default")
      (node (ref "R28") (pin "1") (pinfunction "1_1") (pintype "passive"))
      (node (ref "X16") (pin "1") (pinfunction "1_1") (pintype "passive"))
    )
    (net (code "127") (name "Net-(R30-Pad1)") (class "Default")
      (node (ref "R30") (pin "1") (pinfunction "1_1") (pintype "passive"))
      (node (ref "X16") (pin "3") (pinfunction "3_3") (pintype "passive"))
    )
    (net (code "128") (name "Net-(X10-3)") (class "Default")
      (node (ref "X10") (pin "P$3") (pinfunction "3_P$3") (pintype "bidirectional"))
      (node (ref "X9") (pin "P$4") (pinfunction "4_P$4") (pintype "bidirectional"))
    )
    (net (code "129") (name "Net-(X11-4)") (class "Default")
      (node (ref "X11") (pin "P$4") (pinfunction "4_P$4") (pintype "bidirectional"))
      (node (ref "X12") (pin "P$3") (pinfunction "3_P$3") (pintype "bidirectional"))
    )
    (net (code "130") (name "Net-(X17-3)") (class "Default")
      (node (ref "R32") (pin "2") (pinfunction "2_2") (pintype "passive"))
      (node (ref "R33") (pin "2") (pinfunction "2_2") (pintype "passive"))
      (node (ref "X17") (pin "P$3") (pinfunction "3_P$3") (pintype "bidirectional"))
    )
    (net (code "131") (name "PC9") (class "Default")
      (node (ref "PROZ1") (pin "55") (pinfunction "PC9_55") (pintype "bidirectional"))
    )
    (net (code "132") (name "RM_KVL1") (class "Default")
      (node (ref "PROZ1") (pin "33") (pinfunction "PB14_33") (pintype "bidirectional"))
      (node (ref "Q13") (pin "3") (pinfunction "D_3") (pintype "passive"))
      (node (ref "R73") (pin "1") (pinfunction "1_1") (pintype "passive"))
    )
    (net (code "133") (name "RM_KVL1_EX") (class "Default")
      (node (ref "R74") (pin "2") (pinfunction "2_2") (pintype "passive"))
      (node (ref "R77") (pin "2") (pinfunction "2_2") (pintype "passive"))
      (node (ref "X21") (pin "P$3") (pinfunction "3_P$3") (pintype "bidirectional"))
    )
    (net (code "134") (name "RM_KVL2") (class "Default")
      (node (ref "PROZ1") (pin "34") (pinfunction "PB11_34") (pintype "bidirectional"))
      (node (ref "Q12") (pin "3") (pinfunction "D_3") (pintype "passive"))
      (node (ref "R75") (pin "1") (pinfunction "1_1") (pintype "passive"))
    )
    (net (code "135") (name "RM_KVL2_EX") (class "Default")
      (node (ref "R76") (pin "2") (pinfunction "2_2") (pintype "passive"))
      (node (ref "R78") (pin "2") (pinfunction "2_2") (pintype "passive"))
      (node (ref "X22") (pin "P$3") (pinfunction "3_P$3") (pintype "bidirectional"))
    )
    (net (code "136") (name "SCLK") (class "Default")
      (node (ref "IC15") (pin "5") (pinfunction "SCLK_5") (pintype "bidirectional"))
      (node (ref "IC6") (pin "5") (pinfunction "SCLK_5") (pintype "bidirectional"))
      (node (ref "IC7") (pin "5") (pinfunction "SCLK_5") (pintype "bidirectional"))
      (node (ref "R47") (pin "2") (pinfunction "2_2") (pintype "passive"))
      (node (ref "X5") (pin "P$7") (pinfunction "7_P$7") (pintype "bidirectional"))
    )
    (net (code "137") (name "SCLK_S") (class "Default")
      (node (ref "D11") (pin "P$2") (pinfunction "P$2_P$2") (pintype "bidirectional"))
      (node (ref "PROZ1") (pin "60") (pinfunction "PA5_60") (pintype "bidirectional"))
      (node (ref "R47") (pin "1") (pinfunction "1_1") (pintype "passive"))
    )
    (net (code "138") (name "SLS_CO1") (class "Default")
      (node (ref "IC6") (pin "4") (pinfunction "CO1_4") (pintype "bidirectional"))
      (node (ref "PROZ1") (pin "57") (pinfunction "PA9_57") (pintype "bidirectional"))
    )
    (net (code "139") (name "SLS_RM") (class "Default")
      (node (ref "PROZ1") (pin "56") (pinfunction "PA8_56") (pintype "bidirectional"))
      (node (ref "Q3") (pin "3") (pinfunction "D_3") (pintype "passive"))
      (node (ref "R18") (pin "1") (pinfunction "1_1") (pintype "passive"))
    )
    (net (code "140") (name "SLS_RM_EX") (class "Default")
      (node (ref "R19") (pin "2") (pinfunction "2_2") (pintype "passive"))
      (node (ref "R20") (pin "2") (pinfunction "2_2") (pintype "passive"))
      (node (ref "X9") (pin "P$3") (pinfunction "3_P$3") (pintype "bidirectional"))
    )
    (net (code "141") (name "SPI_CS") (class "Default")
      (node (ref "IC3") (pin "6") (pinfunction "G1_6") (pintype "input"))
      (node (ref "PROZ1") (pin "38") (pinfunction "PB0_38") (pintype "bidirectional"))
    )
    (net (code "142") (name "TS1") (class "Default")
      (node (ref "C21") (pin "2") (pinfunction "2_2") (pintype "passive"))
      (node (ref "D9") (pin "P$2") (pinfunction "P$2_P$2") (pintype "bidirectional"))
      (node (ref "PROZ1") (pin "40") (pinfunction "PC4_40") (pintype "bidirectional"))
      (node (ref "R29") (pin "1") (pinfunction "1_1") (pintype "passive"))
      (node (ref "R30") (pin "2") (pinfunction "2_2") (pintype "passive"))
    )
    (net (code "143") (name "TS2") (class "Default")
      (node (ref "C20") (pin "2") (pinfunction "2_2") (pintype "passive"))
      (node (ref "D10") (pin "P$2") (pinfunction "P$2_P$2") (pintype "bidirectional"))
      (node (ref "PROZ1") (pin "39") (pinfunction "PC5_39") (pintype "bidirectional"))
      (node (ref "R27") (pin "1") (pinfunction "1_1") (pintype "passive"))
      (node (ref "R28") (pin "2") (pinfunction "2_2") (pintype "passive"))
    )
    (net (code "144") (name "USART_RXD") (class "Default")
      (node (ref "PROZ1") (pin "30") (pinfunction "PC11_30") (pintype "bidirectional"))
      (node (ref "X2") (pin "10") (pinfunction "RXD_10") (pintype "passive"))
    )
    (net (code "145") (name "USART_TXD") (class "Default")
      (node (ref "PROZ1") (pin "28") (pinfunction "PC10_28") (pintype "bidirectional"))
      (node (ref "X2") (pin "9") (pinfunction "TXD_9") (pintype "passive"))
    )
    (net (code "146") (name "VBAT") (class "Default")
      (node (ref "C19") (pin "1") (pinfunction "1_1") (pintype "passive"))
      (node (ref "D1") (pin "C") (pinfunction "C_C") (pintype "passive"))
      (node (ref "D2") (pin "C") (pinfunction "C_C") (pintype "passive"))
      (node (ref "IC11") (pin "2") (pinfunction "VIN_2") (pintype "passive"))
      (node (ref "IC12") (pin "P$2") (pinfunction "S_P$2") (pintype "passive"))
      (node (ref "IC13") (pin "1") (pinfunction "VS_1") (pintype "bidirectional"))
      (node (ref "LED10") (pin "A") (pinfunction "A_A") (pintype "passive"))
      (node (ref "LED12") (pin "A") (pinfunction "A_A") (pintype "passive"))
      (node (ref "LED13") (pin "A") (pinfunction "A_A") (pintype "passive"))
      (node (ref "LED6") (pin "A") (pinfunction "A_A") (pintype "passive"))
      (node (ref "LED7") (pin "A") (pinfunction "A_A") (pintype "passive"))
      (node (ref "LED8") (pin "A") (pinfunction "A_A") (pintype "passive"))
      (node (ref "LED9") (pin "A") (pinfunction "A_A") (pintype "passive"))
      (node (ref "R42") (pin "2") (pinfunction "2_2") (pintype "passive"))
      (node (ref "R43") (pin "2") (pinfunction "2_2") (pintype "passive"))
      (node (ref "R44") (pin "2") (pinfunction "2_2") (pintype "passive"))
      (node (ref "TB1") (pin "VIN") (pinfunction "VIN_VIN") (pintype "passive"))
      (node (ref "TERA-DC/DC1") (pin "VIN") (pinfunction "VIN_VIN") (pintype "passive"))
      (node (ref "X1") (pin "2") (pinfunction "2_2") (pintype "passive"))
      (node (ref "X10") (pin "P$2") (pinfunction "2_P$2") (pintype "bidirectional"))
      (node (ref "X10") (pin "P$4") (pinfunction "4_P$4") (pintype "bidirectional"))
      (node (ref "X11") (pin "P$2") (pinfunction "2_P$2") (pintype "bidirectional"))
      (node (ref "X12") (pin "P$2") (pinfunction "2_P$2") (pintype "bidirectional"))
      (node (ref "X12") (pin "P$4") (pinfunction "4_P$4") (pintype "bidirectional"))
      (node (ref "X17") (pin "P$4") (pinfunction "4_P$4") (pintype "bidirectional"))
      (node (ref "X21") (pin "P$2") (pinfunction "2_P$2") (pintype "bidirectional"))
      (node (ref "X21") (pin "P$4") (pinfunction "4_P$4") (pintype "bidirectional"))
      (node (ref "X22") (pin "P$2") (pinfunction "2_P$2") (pintype "bidirectional"))
      (node (ref "X22") (pin "P$4") (pinfunction "4_P$4") (pintype "bidirectional"))
      (node (ref "X3") (pin "4") (pinfunction "V+_4") (pintype "passive"))
      (node (ref "X4") (pin "4") (pinfunction "V+_4") (pintype "passive"))
      (node (ref "X9") (pin "P$2") (pinfunction "2_P$2") (pintype "bidirectional"))
    )
    (net (code "147") (name "VL_CO1") (class "Default")
      (node (ref "IC15") (pin "4") (pinfunction "CO1_4") (pintype "bidirectional"))
      (node (ref "PROZ1") (pin "54") (pinfunction "PC8_54") (pintype "bidirectional"))
    )
    (net (code "148") (name "VREF_PTC_CH") (class "Default")
      (node (ref "C20") (pin "1") (pinfunction "1_1") (pintype "passive"))
      (node (ref "C21") (pin "1") (pinfunction "1_1") (pintype "passive"))
      (node (ref "C22") (pin "1") (pinfunction "1_1") (pintype "passive"))
      (node (ref "IC11") (pin "6") (pinfunction "VOUT_6") (pintype "bidirectional"))
      (node (ref "X16") (pin "2") (pinfunction "2_2") (pintype "passive"))
      (node (ref "X16") (pin "4") (pinfunction "4_4") (pintype "passive"))
    )
    (net (code "149") (name "unconnected-(IC1-VREF-Pad5)") (class "Default")
      (node (ref "IC1") (pin "5") (pinfunction "VREF_5") (pintype "passive"))
    )
    (net (code "150") (name "unconnected-(IC2-VREF-Pad5)") (class "Default")
      (node (ref "IC2") (pin "5") (pinfunction "VREF_5") (pintype "passive"))
    )
    (net (code "151") (name "unconnected-(IC11-~{SHDN}-Pad3)") (class "Default")
      (node (ref "IC11") (pin "3") (pinfunction "~{SHDN}_3") (pintype "passive"))
    )
    (net (code "152") (name "unconnected-(J1-PadP$3)") (class "Default")
      (node (ref "J1") (pin "P$3") (pinfunction "P$3_P$3") (pintype "bidirectional"))
    )
    (net (code "153") (name "unconnected-(J2-PadP$3)") (class "Default")
      (node (ref "J2") (pin "P$3") (pinfunction "P$3_P$3") (pintype "bidirectional"))
    )
    (net (code "154") (name "unconnected-(J3-PadP$3)") (class "Default")
      (node (ref "J3") (pin "P$3") (pinfunction "P$3_P$3") (pintype "bidirectional"))
    )
    (net (code "155") (name "unconnected-(PROZ1F-AGND-Pad1)") (class "Default")
      (node (ref "PROZ1") (pin "1") (pinfunction "AGND_1") (pintype "passive"))
    )
    (net (code "156") (name "unconnected-(PROZ1F-VBAT-Pad6)") (class "Default")
      (node (ref "PROZ1") (pin "6") (pinfunction "VBAT_6") (pintype "passive"))
    )
    (net (code "157") (name "unconnected-(PROZ1F-VDDA_IN-Pad2)") (class "Default")
      (node (ref "PROZ1") (pin "2") (pinfunction "VDDA_IN_2") (pintype "passive"))
    )
    (net (code "158") (name "unconnected-(PROZ1F-VDDA_OUT-Pad4)") (class "Default")
      (node (ref "PROZ1") (pin "4") (pinfunction "VDDA_OUT_4") (pintype "passive"))
    )
  )
)
